# e-ink-display-v003.net
KiCad netlist of a schematic drawn in EAGLE
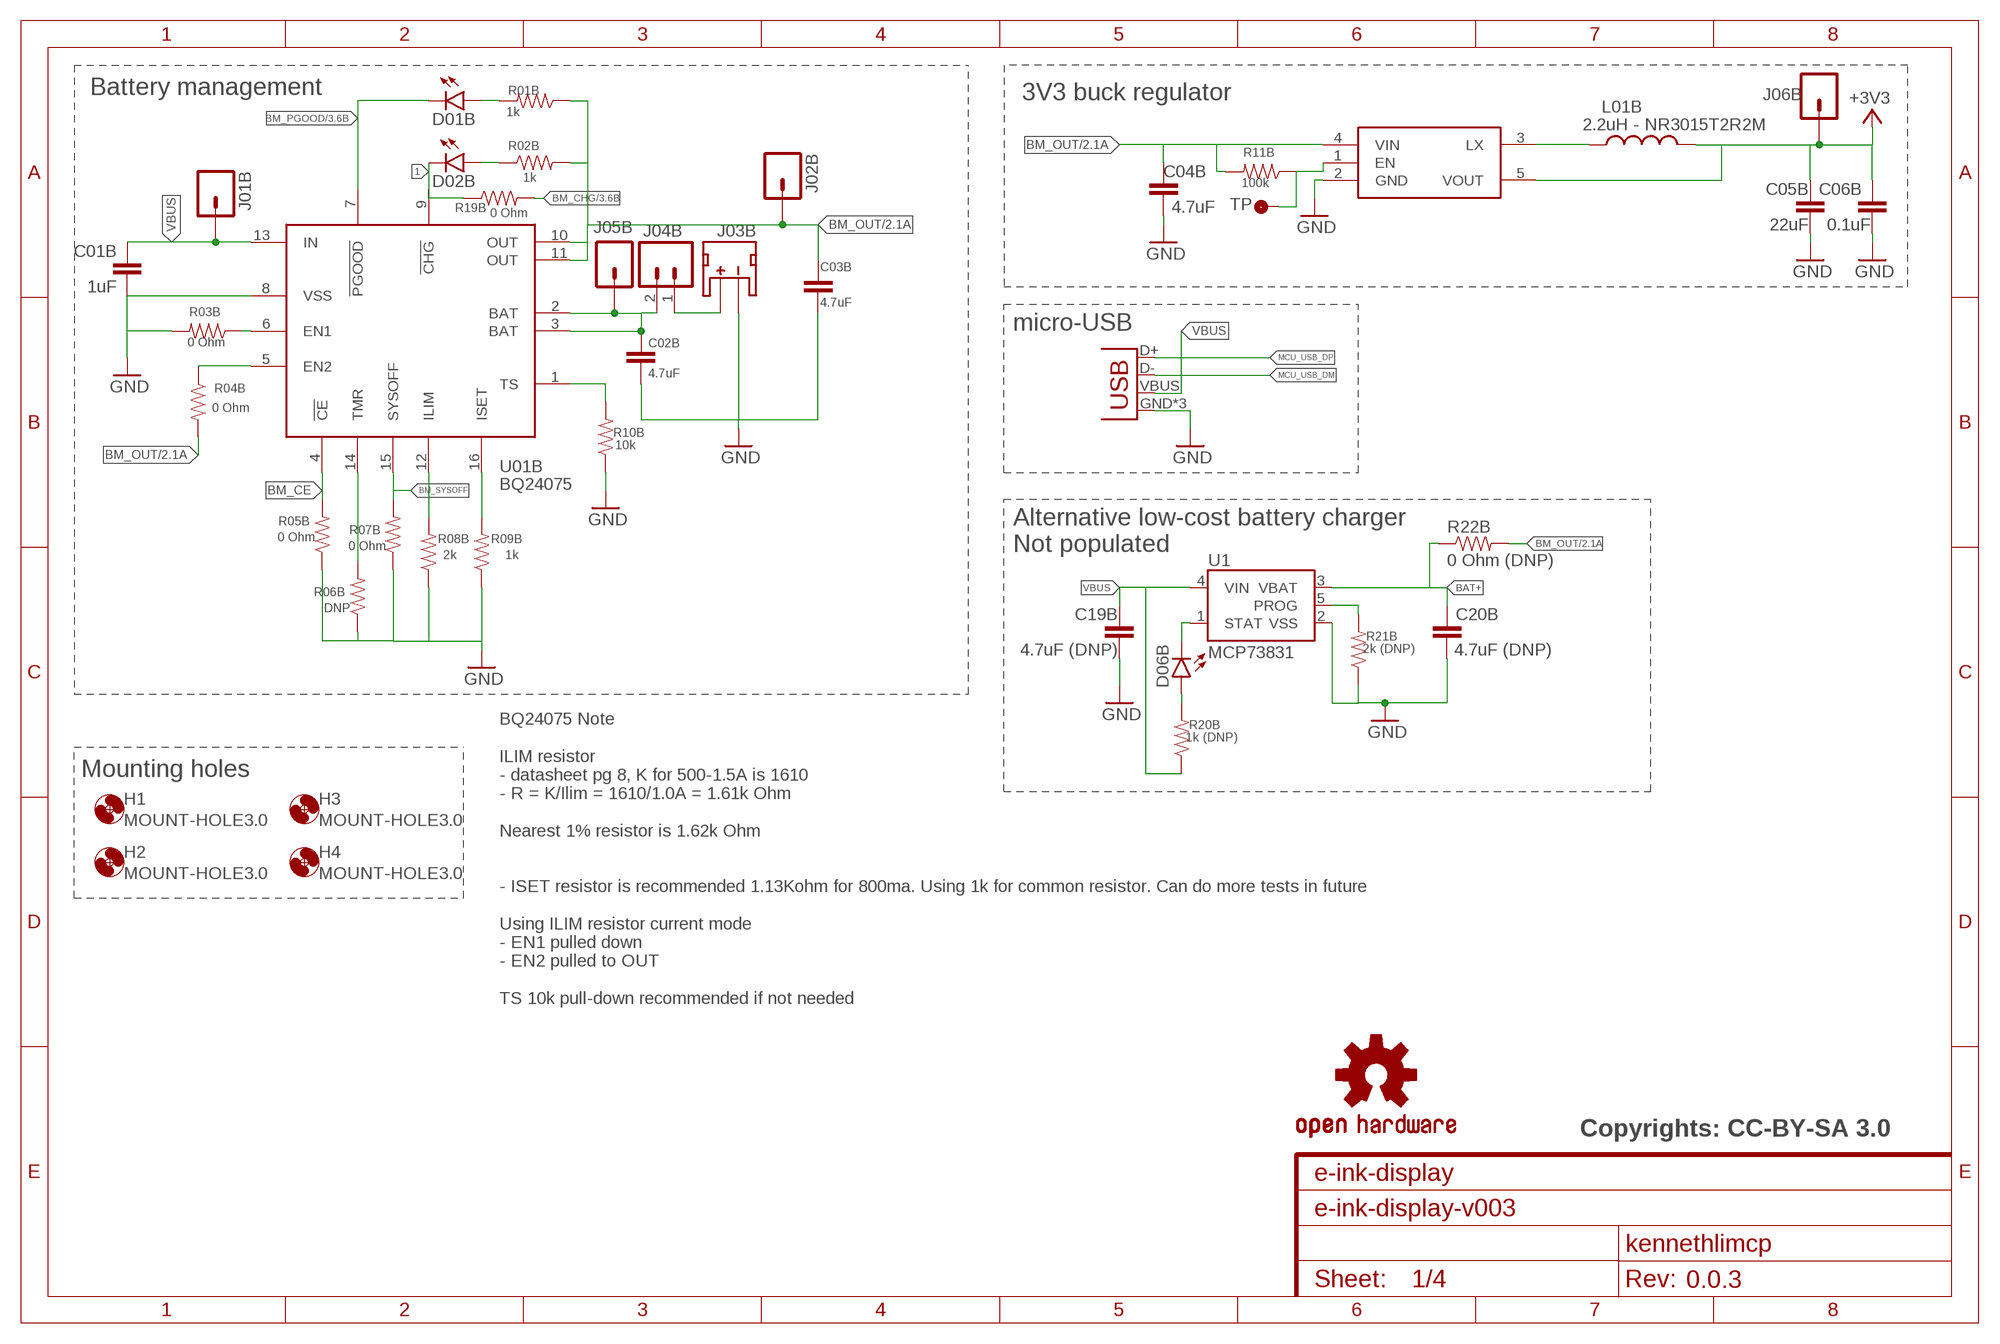
[diagram p0: schematic, sheet 1]
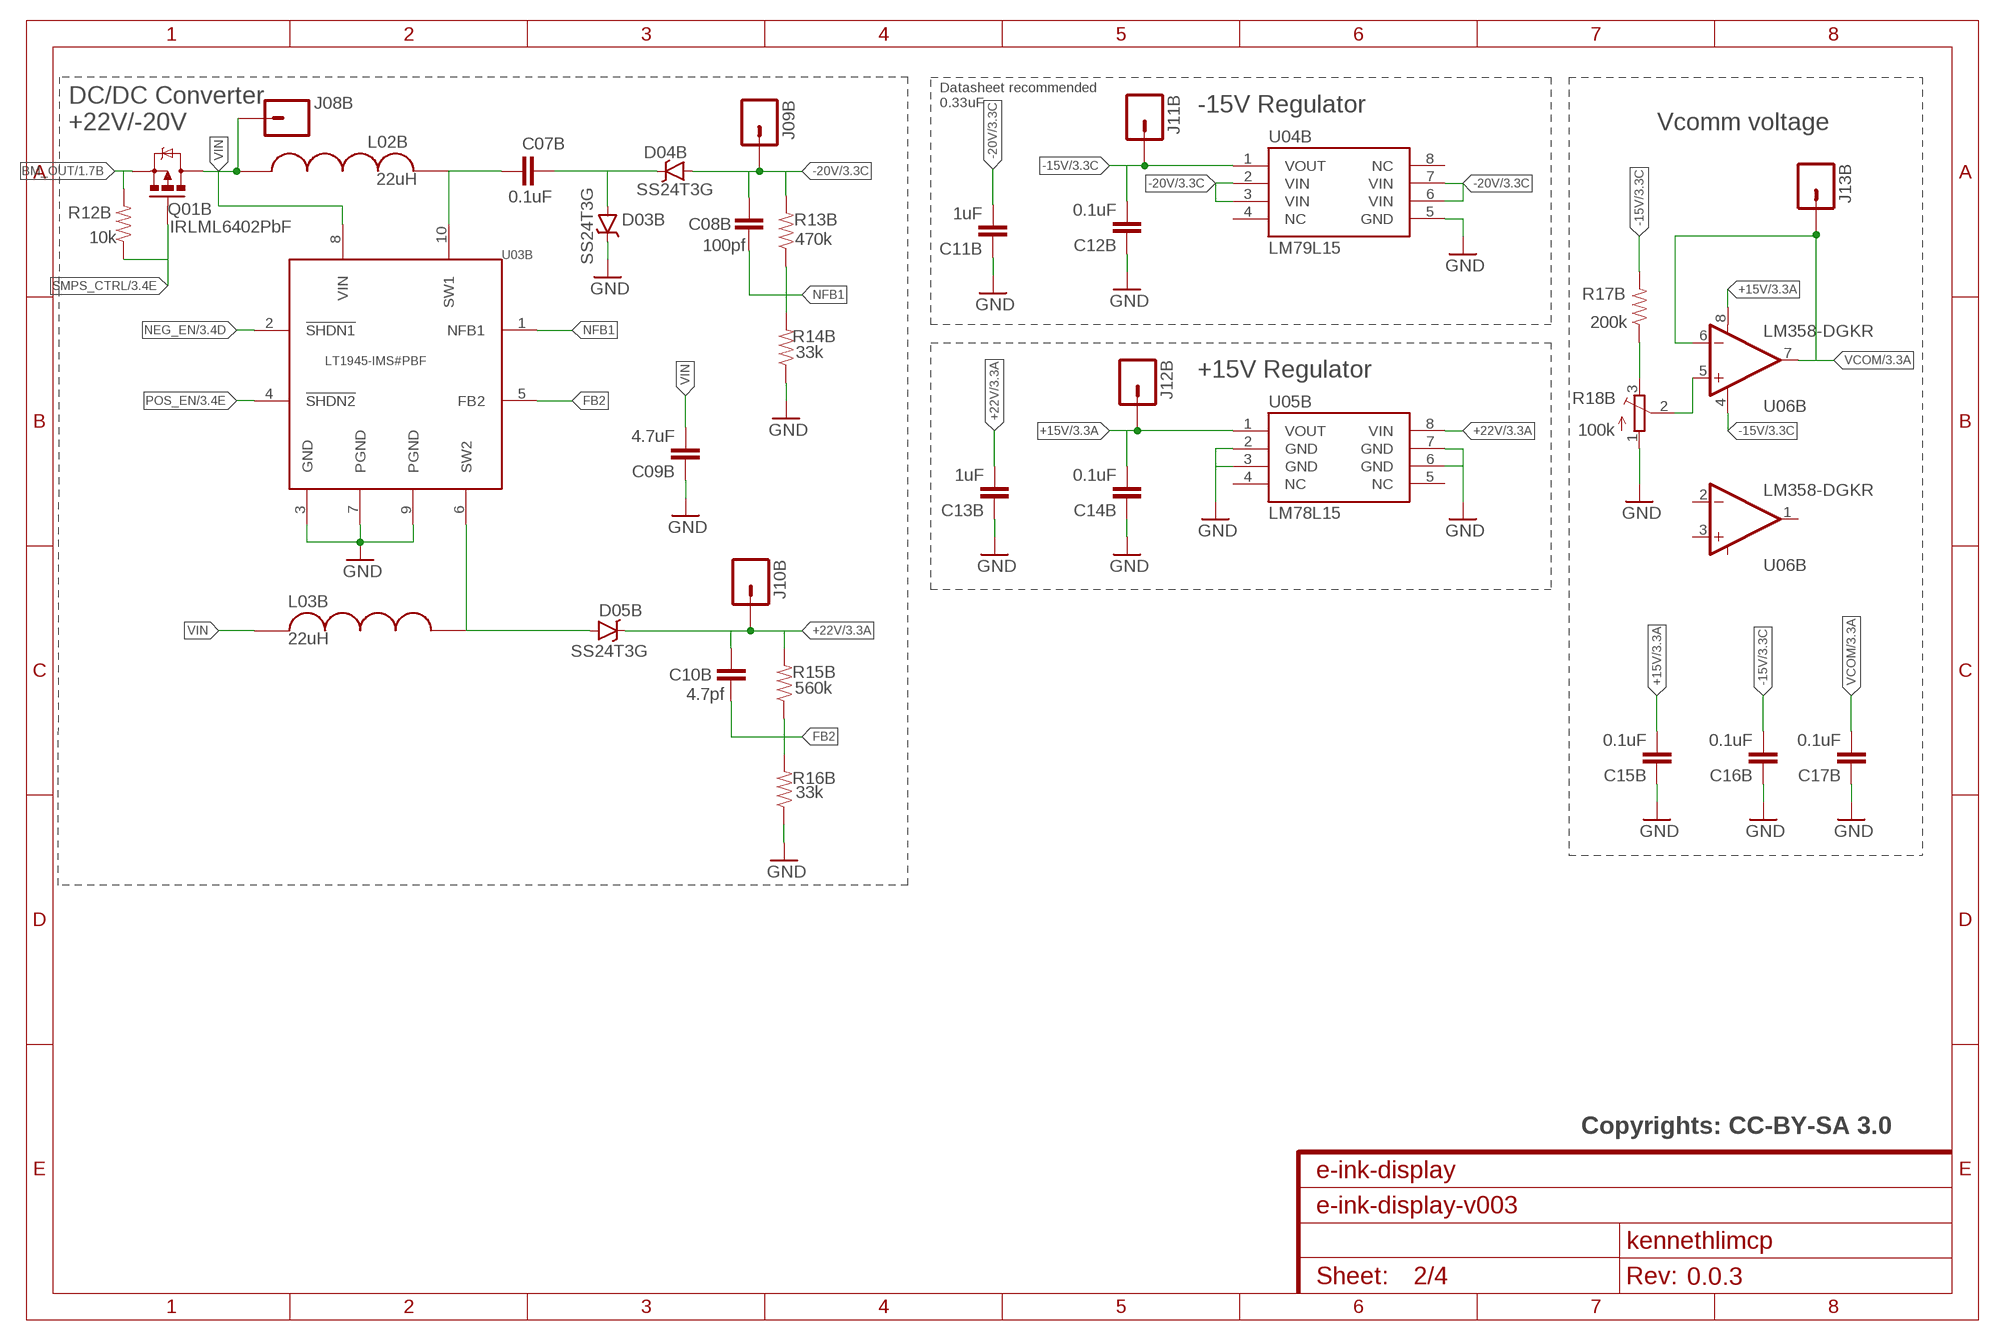
[diagram p1: schematic, sheet 2]
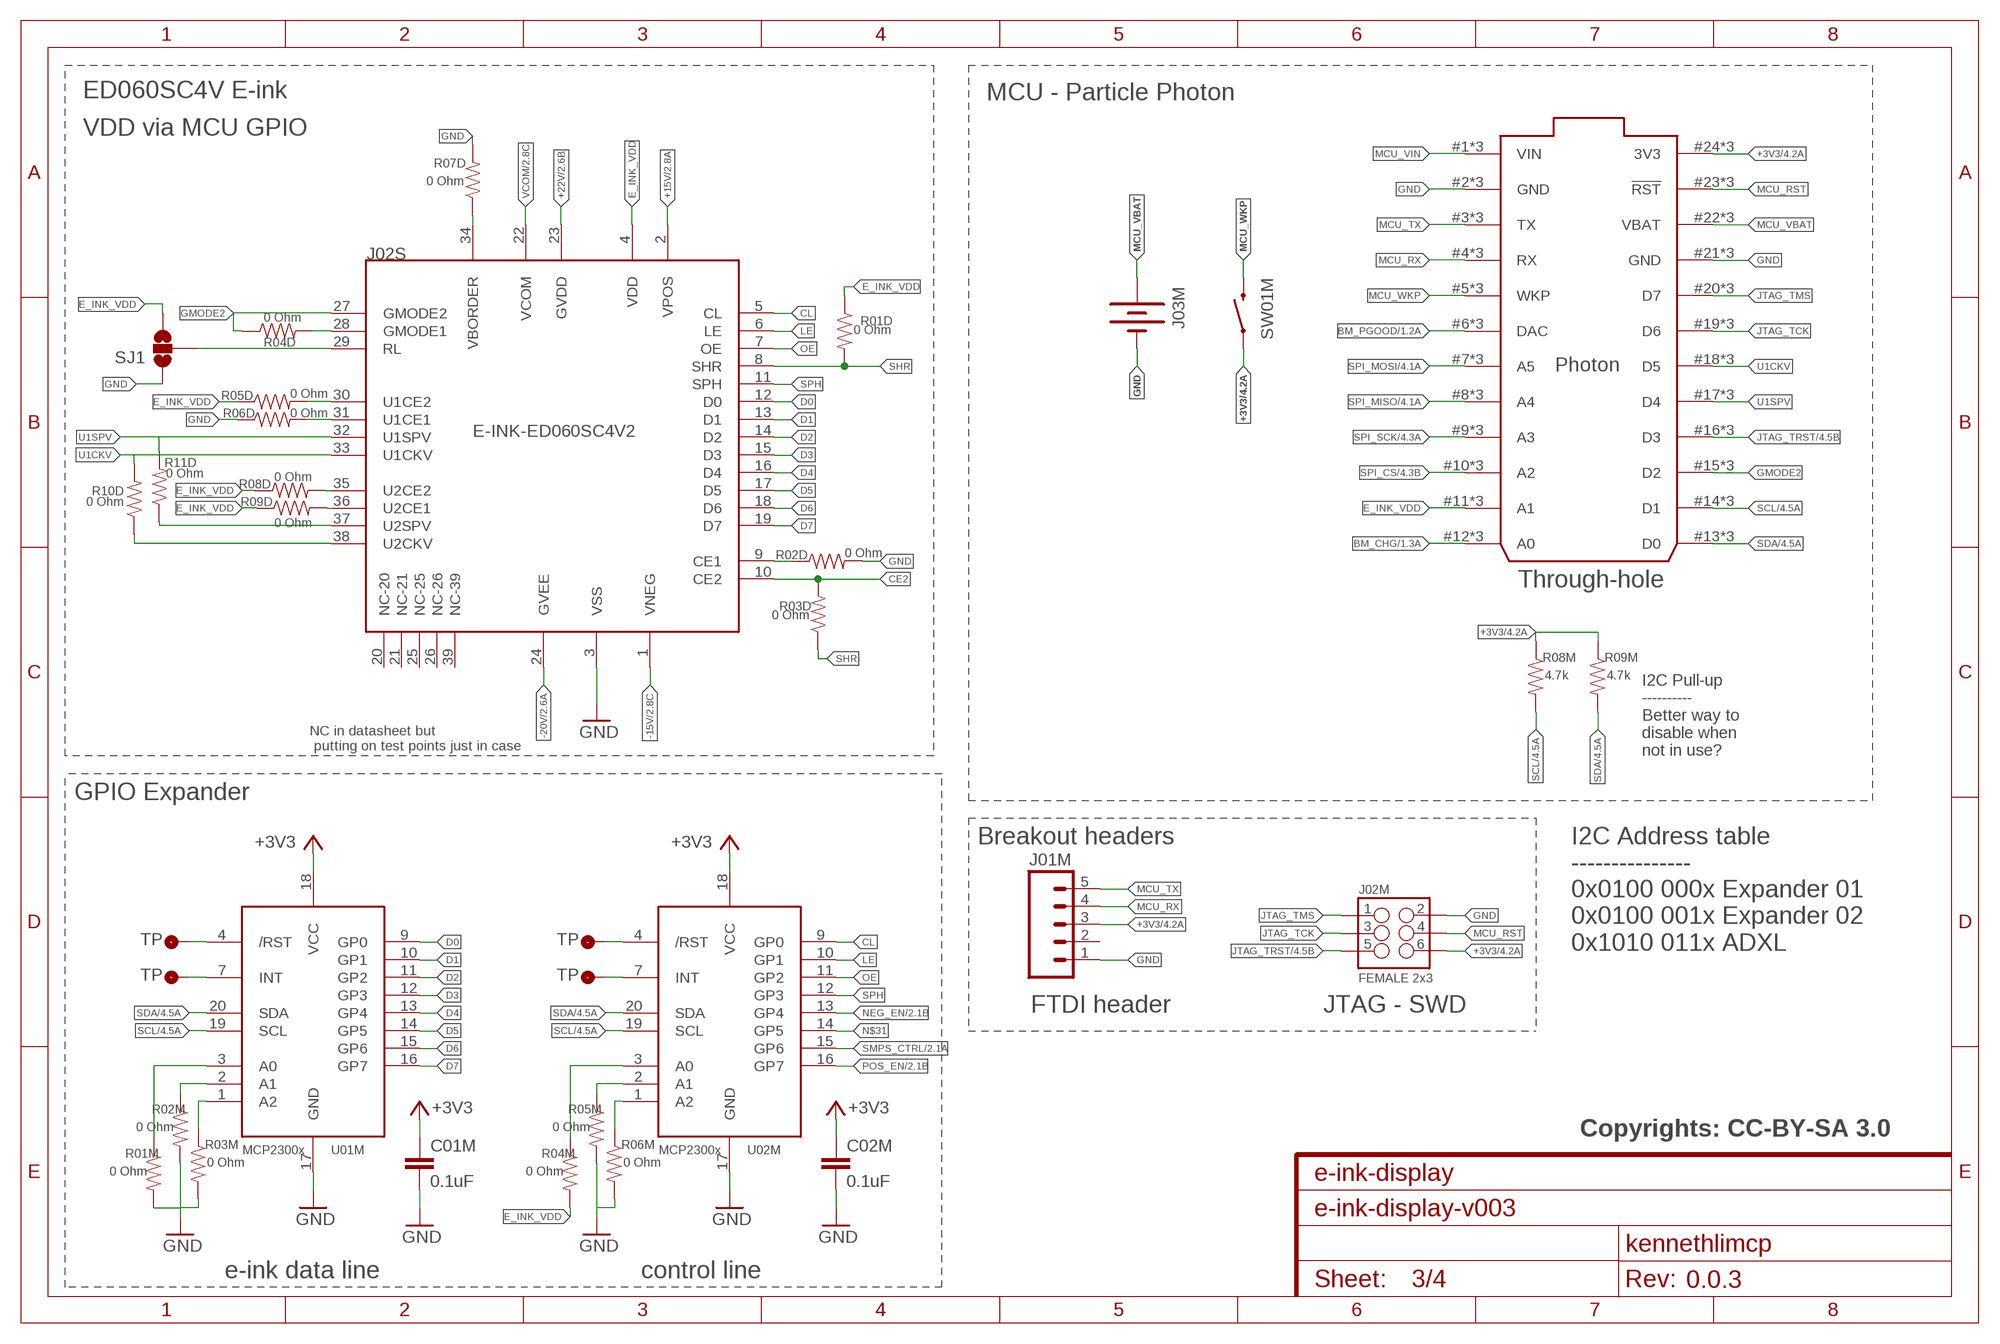
[diagram p2: schematic, sheet 3]
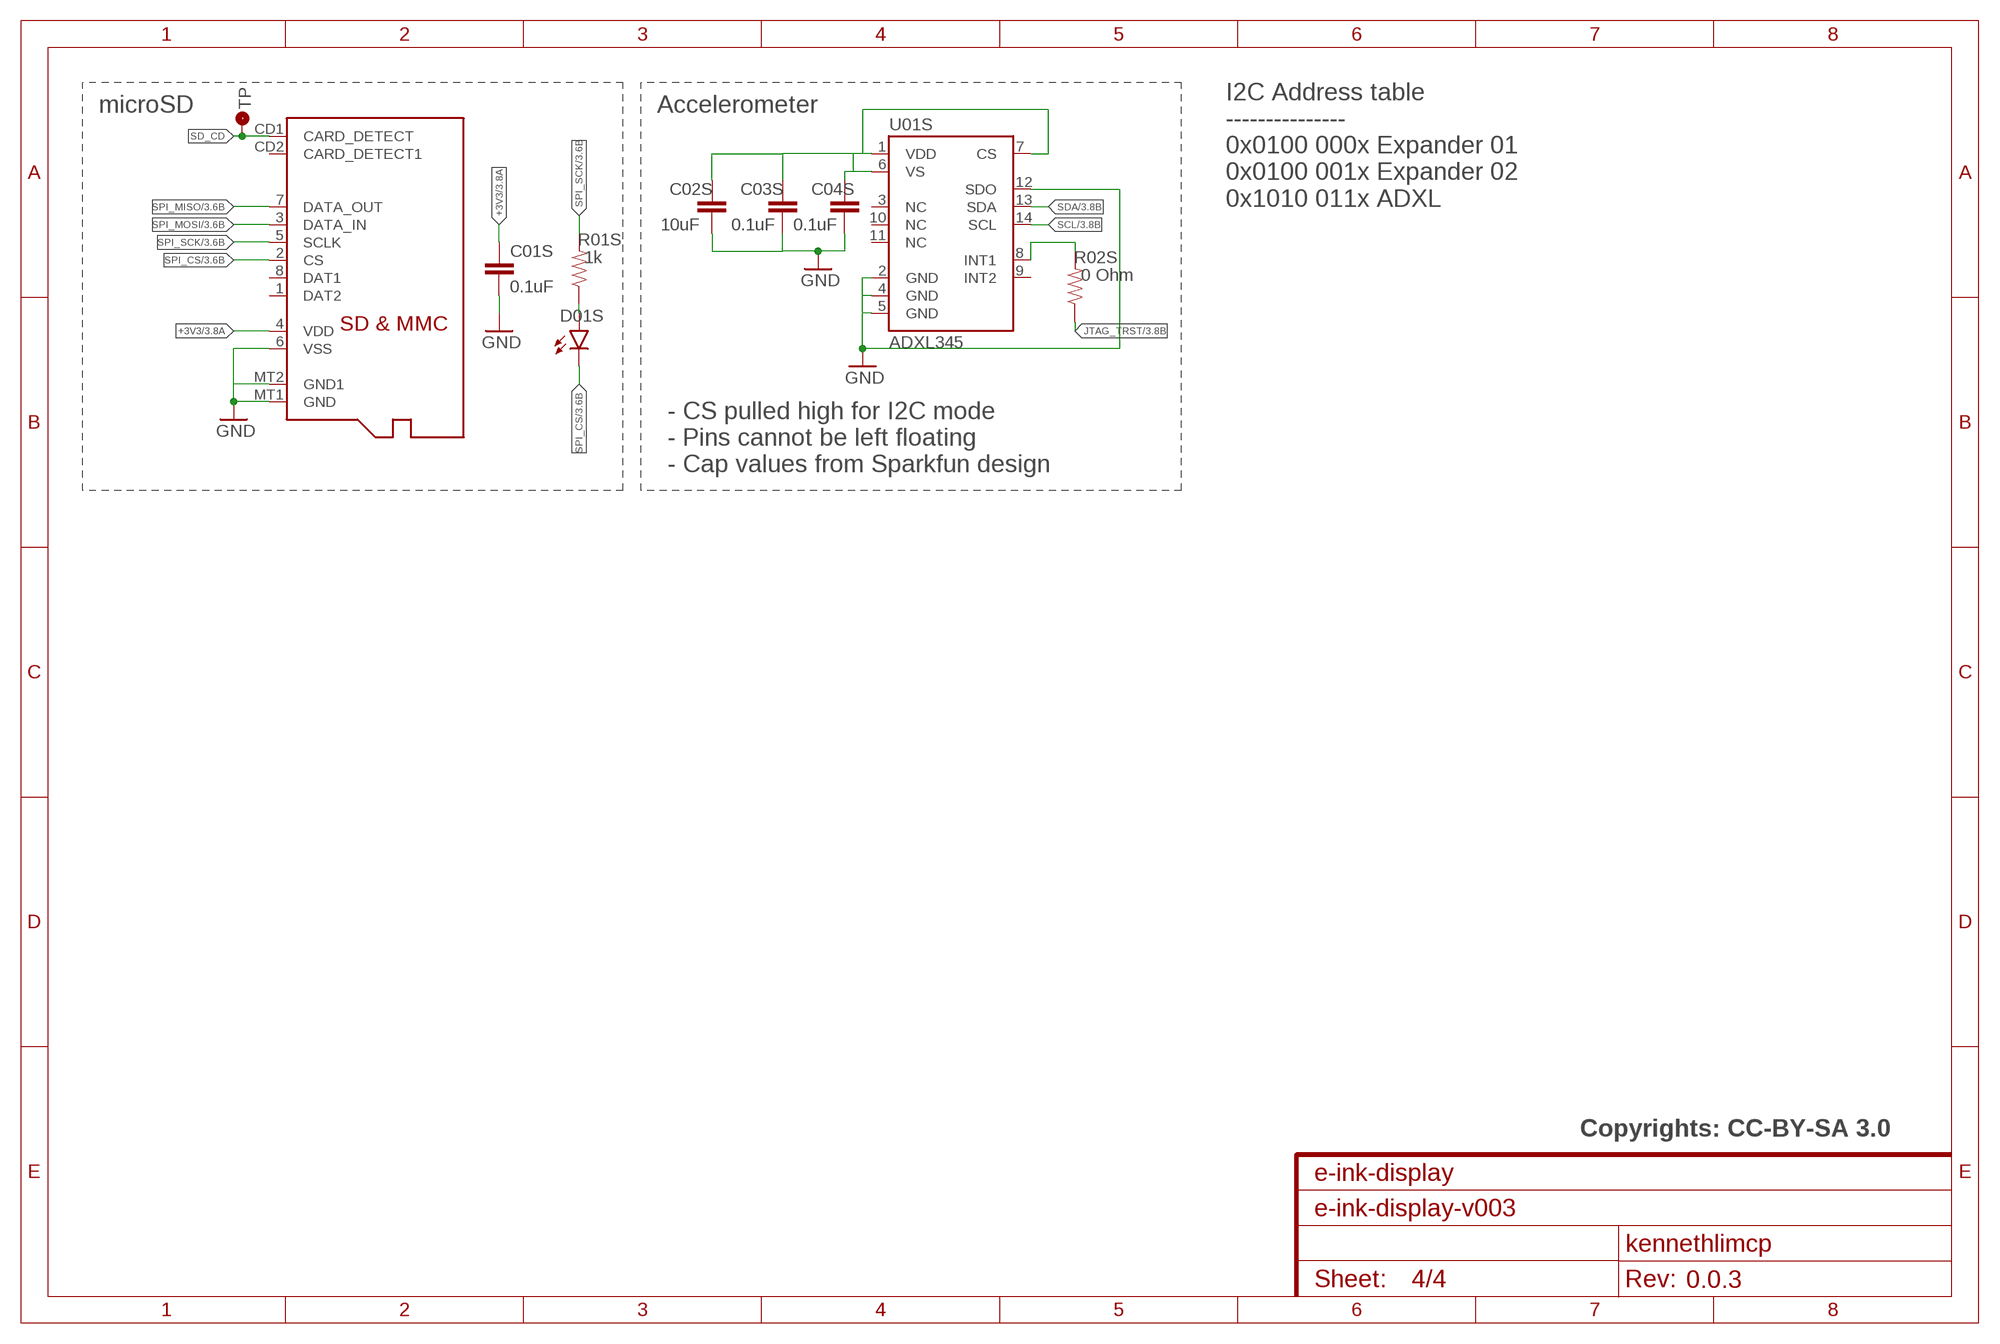
[diagram p3: schematic, sheet 4]

(export (version "E")
  (design (tool "Eeschema 10.0.6"))
  (components
    (comp (ref "C01M")
      (value "0.1uF")
      (footprint "eagle-import:0603-CAP")
      (libsource (lib "eagle-import") (part "CAP0603-CAP"))
    )
    (comp (ref "C02M")
      (value "0.1uF")
      (footprint "eagle-import:0603-CAP")
      (libsource (lib "eagle-import") (part "CAP0603-CAP"))
    )
    (comp (ref "J01M")
      (value "M05PTH")
      (footprint "eagle-import:1X05")
      (libsource (lib "eagle-import") (part "M05PTH"))
    )
    (comp (ref "J02M")
      (value "FEMALE 2x3")
      (footprint "eagle-import:2X3")
      (libsource (lib "eagle-import") (part "M03X2FEMALE"))
    )
    (comp (ref "J02S")
      (value "E-INK-ED060SC4V2")
      (footprint "eagle-import:FPC-0.3-39")
      (libsource (lib "eagle-import") (part "E-INK-ED060SC4V2"))
    )
    (comp (ref "J03M")
      (value "BATTERY20PTH")
      (footprint "eagle-import:BATTCOM_20MM_PTH")
      (libsource (lib "eagle-import") (part "BATTERY20PTH"))
    )
    (comp (ref "R01D")
      (value "0 Ohm")
      (footprint "eagle-import:0603-RES")
      (libsource (lib "eagle-import") (part "RESISTOR0603-RES"))
    )
    (comp (ref "R01M")
      (value "0 Ohm")
      (footprint "eagle-import:0603-RES")
      (libsource (lib "eagle-import") (part "RESISTOR0603-RES"))
    )
    (comp (ref "R02D")
      (value "0 Ohm")
      (footprint "eagle-import:0603-RES")
      (libsource (lib "eagle-import") (part "RESISTOR0603-RES"))
    )
    (comp (ref "R02M")
      (value "0 Ohm")
      (footprint "eagle-import:0603-RES")
      (libsource (lib "eagle-import") (part "RESISTOR0603-RES"))
    )
    (comp (ref "R03D")
      (value "0 Ohm")
      (footprint "eagle-import:0603-RES")
      (libsource (lib "eagle-import") (part "RESISTOR0603-RES"))
    )
    (comp (ref "R03M")
      (value "0 Ohm")
      (footprint "eagle-import:0603-RES")
      (libsource (lib "eagle-import") (part "RESISTOR0603-RES"))
    )
    (comp (ref "R04D")
      (value "0 Ohm")
      (footprint "eagle-import:0603-RES")
      (libsource (lib "eagle-import") (part "RESISTOR0603-RES"))
    )
    (comp (ref "R04M")
      (value "0 Ohm")
      (footprint "eagle-import:0603-RES")
      (libsource (lib "eagle-import") (part "RESISTOR0603-RES"))
    )
    (comp (ref "R05D")
      (value "0 Ohm")
      (footprint "eagle-import:0603-RES")
      (libsource (lib "eagle-import") (part "RESISTOR0603-RES"))
    )
    (comp (ref "R05M")
      (value "0 Ohm")
      (footprint "eagle-import:0603-RES")
      (libsource (lib "eagle-import") (part "RESISTOR0603-RES"))
    )
    (comp (ref "R06D")
      (value "0 Ohm")
      (footprint "eagle-import:0603-RES")
      (libsource (lib "eagle-import") (part "RESISTOR0603-RES"))
    )
    (comp (ref "R06M")
      (value "0 Ohm")
      (footprint "eagle-import:0603-RES")
      (libsource (lib "eagle-import") (part "RESISTOR0603-RES"))
    )
    (comp (ref "R07D")
      (value "0 Ohm")
      (footprint "eagle-import:0603-RES")
      (libsource (lib "eagle-import") (part "RESISTOR0603-RES"))
    )
    (comp (ref "R08D")
      (value "0 Ohm")
      (footprint "eagle-import:0603-RES")
      (libsource (lib "eagle-import") (part "RESISTOR0603-RES"))
    )
    (comp (ref "R08M")
      (value "4.7k")
      (footprint "eagle-import:0603-RES")
      (libsource (lib "eagle-import") (part "RESISTOR0603-RES"))
    )
    (comp (ref "R09D")
      (value "0 Ohm")
      (footprint "eagle-import:0603-RES")
      (libsource (lib "eagle-import") (part "RESISTOR0603-RES"))
    )
    (comp (ref "R09M")
      (value "4.7k")
      (footprint "eagle-import:0603-RES")
      (libsource (lib "eagle-import") (part "RESISTOR0603-RES"))
    )
    (comp (ref "R10D")
      (value "0 Ohm")
      (footprint "eagle-import:0603-RES")
      (libsource (lib "eagle-import") (part "RESISTOR0603-RES"))
    )
    (comp (ref "R11D")
      (value "0 Ohm")
      (footprint "eagle-import:0603-RES")
      (libsource (lib "eagle-import") (part "RESISTOR0603-RES"))
    )
    (comp (ref "SJ1")
      (value "SOLDERJUMPER_2WAYT")
      (footprint "eagle-import:SJ_2")
      (libsource (lib "eagle-import") (part "SOLDERJUMPER_2WAYT"))
    )
    (comp (ref "SW01M")
      (value "SWITCH-MOMENTARY-2PTH")
      (footprint "eagle-import:TACTILE-PTH")
      (libsource (lib "eagle-import") (part "SWITCH-MOMENTARY-2PTH"))
    )
    (comp (ref "U$1")
      (value "TP1")
      (footprint "eagle-import:TP35_BOT")
      (libsource (lib "eagle-import") (part "TP1"))
    )
    (comp (ref "U$2")
      (value "TP1")
      (footprint "eagle-import:TP35_BOT")
      (libsource (lib "eagle-import") (part "TP1"))
    )
    (comp (ref "U$3")
      (value "TP1")
      (footprint "eagle-import:TP35_BOT")
      (libsource (lib "eagle-import") (part "TP1"))
    )
    (comp (ref "U$4")
      (value "TP1")
      (footprint "eagle-import:TP35_BOT")
      (libsource (lib "eagle-import") (part "TP1"))
    )
    (comp (ref "U01M")
      (value "MCP2300X/QFN")
      (footprint "eagle-import:QFN-20(4X4)")
      (libsource (lib "eagle-import") (part "MCP2300X/QFN"))
    )
    (comp (ref "U02M")
      (value "MCP2300X/QFN")
      (footprint "eagle-import:QFN-20(4X4)")
      (libsource (lib "eagle-import") (part "MCP2300X/QFN"))
    )
    (comp (ref "U03M")
      (value "PHOTON_WITH_STACKABLE_HEADERS")
      (footprint "eagle-import:PHOTON_STACKABLE")
      (libsource (lib "eagle-import") (part "PHOTON_WITH_STACKABLE_HEADERS"))
    )
    (comp (ref "C01S")
      (value "0.1uF")
      (footprint "eagle-import:0603-CAP")
      (libsource (lib "eagle-import") (part "CAP0603-CAP"))
    )
    (comp (ref "C02S")
      (value "10uF")
      (footprint "eagle-import:0603-CAP")
      (libsource (lib "eagle-import") (part "CAP0603-CAP"))
    )
    (comp (ref "C03S")
      (value "0.1uF")
      (footprint "eagle-import:0603-CAP")
      (libsource (lib "eagle-import") (part "CAP0603-CAP"))
    )
    (comp (ref "C04S")
      (value "0.1uF")
      (footprint "eagle-import:0603-CAP")
      (libsource (lib "eagle-import") (part "CAP0603-CAP"))
    )
    (comp (ref "D01S")
      (value "LED0603")
      (footprint "eagle-import:LED-0603")
      (libsource (lib "eagle-import") (part "LED0603"))
    )
    (comp (ref "J01S")
      (value "MICROSD")
      (footprint "eagle-import:MICROSD")
      (libsource (lib "eagle-import") (part "MICROSD"))
    )
    (comp (ref "R01S")
      (value "1k")
      (footprint "eagle-import:0603-RES")
      (libsource (lib "eagle-import") (part "SparkFun-Resistors_RESISTOR0603-RES"))
    )
    (comp (ref "R02S")
      (value "0 Ohm")
      (footprint "eagle-import:0603-RES")
      (libsource (lib "eagle-import") (part "RESISTOR0603"))
    )
    (comp (ref "U$5")
      (value "TP3")
      (footprint "eagle-import:TP60_BOT")
      (libsource (lib "eagle-import") (part "TP3"))
    )
    (comp (ref "U01S")
      (value "ADXL345")
      (footprint "eagle-import:LGA14")
      (libsource (lib "eagle-import") (part "ADXL345"))
    )
    (comp (ref "C01B")
      (value "1uF")
      (footprint "eagle-import:0603-CAP")
      (libsource (lib "eagle-import") (part "CAP0603-CAP"))
    )
    (comp (ref "C02B")
      (value "4.7uF")
      (footprint "eagle-import:0603-CAP")
      (libsource (lib "eagle-import") (part "CAP0603-CAP"))
    )
    (comp (ref "C03B")
      (value "4.7uF")
      (footprint "eagle-import:0603-CAP")
      (libsource (lib "eagle-import") (part "CAP0603-CAP"))
    )
    (comp (ref "C04B")
      (value "4.7uF")
      (footprint "eagle-import:0603-CAP")
      (libsource (lib "eagle-import") (part "CAP0603-CAP"))
    )
    (comp (ref "C05B")
      (value "22uF")
      (footprint "eagle-import:0603-CAP")
      (libsource (lib "eagle-import") (part "CAP0603-CAP"))
    )
    (comp (ref "C06B")
      (value "0.1uF")
      (footprint "eagle-import:0603-CAP")
      (libsource (lib "eagle-import") (part "CAP0603-CAP"))
    )
    (comp (ref "C19B")
      (value "4.7uF (DNP)")
      (footprint "eagle-import:0603-CAP")
      (libsource (lib "eagle-import") (part "CAP0603-CAP"))
    )
    (comp (ref "C20B")
      (value "4.7uF (DNP)")
      (footprint "eagle-import:0603-CAP")
      (libsource (lib "eagle-import") (part "CAP0603-CAP"))
    )
    (comp (ref "D01B")
      (value "LED0603")
      (footprint "eagle-import:LED-0603")
      (libsource (lib "eagle-import") (part "LED0603"))
    )
    (comp (ref "D02B")
      (value "LED0603")
      (footprint "eagle-import:LED-0603")
      (libsource (lib "eagle-import") (part "LED0603"))
    )
    (comp (ref "D06B")
      (value "LED0603")
      (footprint "eagle-import:LED-0603")
      (libsource (lib "eagle-import") (part "LED0603"))
    )
    (comp (ref "H1")
      (value "MOUNT-HOLE3.0")
      (footprint "eagle-import:3,0")
      (libsource (lib "eagle-import") (part "MOUNT-HOLE3.0"))
    )
    (comp (ref "H2")
      (value "MOUNT-HOLE3.0")
      (footprint "eagle-import:3,0")
      (libsource (lib "eagle-import") (part "MOUNT-HOLE3.0"))
    )
    (comp (ref "H3")
      (value "MOUNT-HOLE3.0")
      (footprint "eagle-import:3,0")
      (libsource (lib "eagle-import") (part "MOUNT-HOLE3.0"))
    )
    (comp (ref "H4")
      (value "MOUNT-HOLE3.0")
      (footprint "eagle-import:3,0")
      (libsource (lib "eagle-import") (part "MOUNT-HOLE3.0"))
    )
    (comp (ref "J01B")
      (value "M01PTH")
      (footprint "eagle-import:1X01")
      (libsource (lib "eagle-import") (part "M01PTH"))
    )
    (comp (ref "J02B")
      (value "M01PTH")
      (footprint "eagle-import:1X01")
      (libsource (lib "eagle-import") (part "M01PTH"))
    )
    (comp (ref "J03B")
      (value "JST_2MM_MALE")
      (footprint "eagle-import:JST-2-SMD")
      (libsource (lib "eagle-import") (part "JST_2MM_MALE"))
    )
    (comp (ref "J04B")
      (value "M02PTH")
      (footprint "eagle-import:1X02")
      (libsource (lib "eagle-import") (part "M02PTH"))
    )
    (comp (ref "J05B")
      (value "M01PTH")
      (footprint "eagle-import:1X01")
      (libsource (lib "eagle-import") (part "M01PTH"))
    )
    (comp (ref "J06B")
      (value "M01PTH")
      (footprint "eagle-import:1X01")
      (libsource (lib "eagle-import") (part "M01PTH"))
    )
    (comp (ref "J07B")
      (value "USBUSB-MICROB-SLOT-HOLE")
      (footprint "eagle-import:USB-MICROB-SLOT-HOLE")
      (libsource (lib "eagle-import") (part "USBUSB-MICROB-SLOT-HOLE"))
    )
    (comp (ref "L01B")
      (value "2.2uH - NR3015T2R2M")
      (footprint "eagle-import:INDUCTOR-NR3015")
      (libsource (lib "eagle-import") (part "INDUCTOR-SPARKFUNNR3015T4R7M"))
    )
    (comp (ref "LOGO1")
      (value "OSHW-LOGOPAD")
      (footprint "eagle-import:OSHW-LOGO-M-PAD")
      (libsource (lib "eagle-import") (part "OSHW-LOGOPAD"))
    )
    (comp (ref "R01B")
      (value "1k")
      (footprint "eagle-import:0603-RES")
      (libsource (lib "eagle-import") (part "SparkFun-Resistors_RESISTOR0603-RES"))
    )
    (comp (ref "R02B")
      (value "1k")
      (footprint "eagle-import:0603-RES")
      (libsource (lib "eagle-import") (part "SparkFun-Resistors_RESISTOR0603-RES"))
    )
    (comp (ref "R03B")
      (value "0 Ohm")
      (footprint "eagle-import:0603-RES")
      (libsource (lib "eagle-import") (part "SparkFun-Resistors_RESISTOR0603-RES"))
    )
    (comp (ref "R04B")
      (value "0 Ohm")
      (footprint "eagle-import:0603-RES")
      (libsource (lib "eagle-import") (part "RESISTOR0603"))
    )
    (comp (ref "R05B")
      (value "0 Ohm")
      (footprint "eagle-import:0603-RES")
      (libsource (lib "eagle-import") (part "RESISTOR0603"))
    )
    (comp (ref "R06B")
      (value "DNP")
      (footprint "eagle-import:0603-RES")
      (libsource (lib "eagle-import") (part "RESISTOR0603"))
    )
    (comp (ref "R07B")
      (value "0 Ohm")
      (footprint "eagle-import:0603-RES")
      (libsource (lib "eagle-import") (part "RESISTOR0603"))
    )
    (comp (ref "R08B")
      (value "2k")
      (footprint "eagle-import:0603-RES")
      (libsource (lib "eagle-import") (part "RESISTOR0603"))
    )
    (comp (ref "R09B")
      (value "1k")
      (footprint "eagle-import:0603-RES")
      (libsource (lib "eagle-import") (part "SparkFun-Resistors_RESISTOR0603-RES"))
    )
    (comp (ref "R10B")
      (value "10k")
      (footprint "eagle-import:0603-RES")
      (libsource (lib "eagle-import") (part "RESISTOR0603"))
    )
    (comp (ref "R11B")
      (value "100k")
      (footprint "eagle-import:0603-RES")
      (libsource (lib "eagle-import") (part "RESISTOR0603"))
    )
    (comp (ref "R19B")
      (value "0 Ohm")
      (footprint "eagle-import:0603-RES")
      (libsource (lib "eagle-import") (part "RESISTOR0603"))
    )
    (comp (ref "R20B")
      (value "1k (DNP)")
      (footprint "eagle-import:0603-RES")
      (libsource (lib "eagle-import") (part "RESISTOR0603"))
    )
    (comp (ref "R21B")
      (value "2k (DNP)")
      (footprint "eagle-import:0603-RES")
      (libsource (lib "eagle-import") (part "RESISTOR0603"))
    )
    (comp (ref "R22B")
      (value "0 Ohm (DNP)")
      (footprint "eagle-import:1206")
      (libsource (lib "eagle-import") (part "SparkFun-Resistors_RESISTOR1206"))
    )
    (comp (ref "TP01B")
      (value "TP1")
      (footprint "eagle-import:TP35_BOT")
      (libsource (lib "eagle-import") (part "TP1"))
    )
    (comp (ref "U1")
      (value "MCP73831")
      (footprint "eagle-import:SOT23-5")
      (libsource (lib "eagle-import") (part "MCP73831"))
    )
    (comp (ref "U01B")
      (value "BQ24075")
      (footprint "eagle-import:QFN-16")
      (libsource (lib "eagle-import") (part "BQ24075"))
    )
    (comp (ref "U02B")
      (value "R8008-33")
      (footprint "eagle-import:SOT23-5")
      (libsource (lib "eagle-import") (part "R8008-33"))
    )
    (comp (ref "C07B")
      (value "0.1uF")
      (footprint "eagle-import:0603-CAP")
      (libsource (lib "eagle-import") (part "CAP0603-CAP"))
    )
    (comp (ref "C08B")
      (value "100pf")
      (footprint "eagle-import:0603-CAP")
      (libsource (lib "eagle-import") (part "CAP0603-CAP"))
    )
    (comp (ref "C09B")
      (value "4.7uF")
      (footprint "eagle-import:0603-CAP")
      (libsource (lib "eagle-import") (part "CAP0603-CAP"))
    )
    (comp (ref "C10B")
      (value "4.7pf")
      (footprint "eagle-import:0603-CAP")
      (libsource (lib "eagle-import") (part "CAP0603-CAP"))
    )
    (comp (ref "C11B")
      (value "1uF")
      (footprint "eagle-import:0603-CAP")
      (libsource (lib "eagle-import") (part "CAP0603-CAP"))
    )
    (comp (ref "C12B")
      (value "0.1uF")
      (footprint "eagle-import:0603-CAP")
      (libsource (lib "eagle-import") (part "CAP0603-CAP"))
    )
    (comp (ref "C13B")
      (value "1uF")
      (footprint "eagle-import:0603-CAP")
      (libsource (lib "eagle-import") (part "CAP0603-CAP"))
    )
    (comp (ref "C14B")
      (value "0.1uF")
      (footprint "eagle-import:0603-CAP")
      (libsource (lib "eagle-import") (part "CAP0603-CAP"))
    )
    (comp (ref "C15B")
      (value "0.1uF")
      (footprint "eagle-import:0603-CAP")
      (libsource (lib "eagle-import") (part "CAP0603-CAP"))
    )
    (comp (ref "C16B")
      (value "0.1uF")
      (footprint "eagle-import:0603-CAP")
      (libsource (lib "eagle-import") (part "CAP0603-CAP"))
    )
    (comp (ref "C17B")
      (value "0.1uF")
      (footprint "eagle-import:0603-CAP")
      (libsource (lib "eagle-import") (part "CAP0603-CAP"))
    )
    (comp (ref "D03B")
      (value "SS24T3G")
      (footprint "eagle-import:SMA-DIODE")
      (libsource (lib "eagle-import") (part "SS24T3G"))
    )
    (comp (ref "D04B")
      (value "SS24T3G")
      (footprint "eagle-import:SMA-DIODE")
      (libsource (lib "eagle-import") (part "SS24T3G"))
    )
    (comp (ref "D05B")
      (value "SS24T3G")
      (footprint "eagle-import:SMA-DIODE")
      (libsource (lib "eagle-import") (part "SS24T3G"))
    )
    (comp (ref "J08B")
      (value "M01PTH")
      (footprint "eagle-import:1X01")
      (libsource (lib "eagle-import") (part "M01PTH"))
    )
    (comp (ref "J09B")
      (value "M01PTH")
      (footprint "eagle-import:1X01")
      (libsource (lib "eagle-import") (part "M01PTH"))
    )
    (comp (ref "J10B")
      (value "M01PTH")
      (footprint "eagle-import:1X01")
      (libsource (lib "eagle-import") (part "M01PTH"))
    )
    (comp (ref "J11B")
      (value "M01PTH")
      (footprint "eagle-import:1X01")
      (libsource (lib "eagle-import") (part "M01PTH"))
    )
    (comp (ref "J12B")
      (value "M01PTH")
      (footprint "eagle-import:1X01")
      (libsource (lib "eagle-import") (part "M01PTH"))
    )
    (comp (ref "J13B")
      (value "M01PTH")
      (footprint "eagle-import:1X01")
      (libsource (lib "eagle-import") (part "M01PTH"))
    )
    (comp (ref "L02B")
      (value "22uH")
      (footprint "eagle-import:4040(1515)")
      (libsource (lib "eagle-import") (part "INDUCTOR"))
    )
    (comp (ref "L03B")
      (value "22uH")
      (footprint "eagle-import:4040(1515)")
      (libsource (lib "eagle-import") (part "INDUCTOR"))
    )
    (comp (ref "Q01B")
      (value "IRLML6402PbF")
      (footprint "eagle-import:SOT23-3")
      (libsource (lib "eagle-import") (part "MOSFET-PCHANNELSMD"))
    )
    (comp (ref "R12B")
      (value "10k")
      (footprint "eagle-import:0603-RES")
      (libsource (lib "eagle-import") (part "RESISTOR0603"))
    )
    (comp (ref "R13B")
      (value "470k")
      (footprint "eagle-import:0603-RES")
      (libsource (lib "eagle-import") (part "RESISTOR0603"))
    )
    (comp (ref "R14B")
      (value "33k")
      (footprint "eagle-import:0603-RES")
      (libsource (lib "eagle-import") (part "RESISTOR0603"))
    )
    (comp (ref "R15B")
      (value "560k")
      (footprint "eagle-import:0603-RES")
      (libsource (lib "eagle-import") (part "RESISTOR0603"))
    )
    (comp (ref "R16B")
      (value "33k")
      (footprint "eagle-import:0603-RES")
      (libsource (lib "eagle-import") (part "RESISTOR0603"))
    )
    (comp (ref "R17B")
      (value "200k")
      (footprint "eagle-import:0603-RES")
      (libsource (lib "eagle-import") (part "RESISTOR0603"))
    )
    (comp (ref "R18B")
      (value "100k")
      (footprint "eagle-import:TC33X")
      (libsource (lib "eagle-import") (part "TRIMPOTTC33X"))
    )
    (comp (ref "U03B")
      (value "LT1945-IMS#PBF")
      (footprint "eagle-import:MSOP-10")
      (libsource (lib "eagle-import") (part "LT1945-IMS#PBF"))
    )
    (comp (ref "U04B")
      (value "LM79L15")
      (footprint "eagle-import:SO08")
      (libsource (lib "eagle-import") (part "LM79L15"))
    )
    (comp (ref "U05B")
      (value "LM78L15")
      (footprint "eagle-import:SO08")
      (libsource (lib "eagle-import") (part "LM78L15"))
    )
    (comp (ref "U06B")
      (value "LM358-DGKR")
      (footprint "eagle-import:MSOP-8")
      (libsource (lib "eagle-import") (part "LM358-DGKR"))
    )
  )
  (nets
    (net (code "1") (name "+3V3") (class "Default")
      (node (ref "C01M") (pin "1") (pinfunction "1_1") (pintype "passive"))
      (node (ref "C01S") (pin "1") (pinfunction "1_1") (pintype "passive"))
      (node (ref "C02M") (pin "1") (pinfunction "1_1") (pintype "passive"))
      (node (ref "C05B") (pin "2") (pinfunction "2_2") (pintype "passive"))
      (node (ref "C06B") (pin "2") (pinfunction "2_2") (pintype "passive"))
      (node (ref "J01M") (pin "3") (pinfunction "3_3") (pintype "passive"))
      (node (ref "J01S") (pin "4") (pinfunction "VDD_4") (pintype "power_in"))
      (node (ref "J02M") (pin "6") (pinfunction "6_6") (pintype "bidirectional"))
      (node (ref "J06B") (pin "1") (pinfunction "1_1") (pintype "passive"))
      (node (ref "L01B") (pin "2") (pinfunction "2_2") (pintype "passive"))
      (node (ref "R08M") (pin "1") (pinfunction "1_1") (pintype "passive"))
      (node (ref "R09M") (pin "1") (pinfunction "1_1") (pintype "passive"))
      (node (ref "SW01M") (pin "1") (pinfunction "1_1") (pintype "passive"))
      (node (ref "U01M") (pin "18") (pinfunction "VCC_18") (pintype "power_in"))
      (node (ref "U02B") (pin "5") (pinfunction "VOUT_5") (pintype "bidirectional"))
      (node (ref "U02M") (pin "18") (pinfunction "VCC_18") (pintype "power_in"))
      (node (ref "U03M") (pin "#24") (pinfunction "3V3_#24") (pintype "power_in"))
      (node (ref "U03M") (pin "24") (pinfunction "3V3_24") (pintype "power_in"))
      (node (ref "U03M") (pin "@24") (pinfunction "3V3_@24") (pintype "power_in"))
    )
    (net (code "2") (name "+15V") (class "Default")
      (node (ref "C14B") (pin "2") (pinfunction "2_2") (pintype "passive"))
      (node (ref "C15B") (pin "2") (pinfunction "2_2") (pintype "passive"))
      (node (ref "J02S") (pin "2") (pinfunction "VPOS_2") (pintype "bidirectional"))
      (node (ref "J12B") (pin "1") (pinfunction "1_1") (pintype "passive"))
      (node (ref "U05B") (pin "1") (pinfunction "VOUT_1") (pintype "bidirectional"))
      (node (ref "U06B") (pin "8") (pinfunction "V+_8") (pintype "power_in"))
    )
    (net (code "3") (name "+22V") (class "Default")
      (node (ref "C10B") (pin "2") (pinfunction "2_2") (pintype "passive"))
      (node (ref "C13B") (pin "2") (pinfunction "2_2") (pintype "passive"))
      (node (ref "D05B") (pin "C") (pinfunction "C_C") (pintype "passive"))
      (node (ref "J02S") (pin "23") (pinfunction "GVDD_23") (pintype "bidirectional"))
      (node (ref "J10B") (pin "1") (pinfunction "1_1") (pintype "passive"))
      (node (ref "R15B") (pin "2") (pinfunction "2_2") (pintype "passive"))
      (node (ref "U05B") (pin "8") (pinfunction "VIN_8") (pintype "bidirectional"))
    )
    (net (code "4") (name "-15V") (class "Default")
      (node (ref "C12B") (pin "2") (pinfunction "2_2") (pintype "passive"))
      (node (ref "C16B") (pin "2") (pinfunction "2_2") (pintype "passive"))
      (node (ref "J02S") (pin "1") (pinfunction "VNEG_1") (pintype "bidirectional"))
      (node (ref "J11B") (pin "1") (pinfunction "1_1") (pintype "passive"))
      (node (ref "R17B") (pin "2") (pinfunction "2_2") (pintype "passive"))
      (node (ref "U04B") (pin "1") (pinfunction "VOUT_1") (pintype "bidirectional"))
      (node (ref "U06B") (pin "4") (pinfunction "V-_4") (pintype "power_in"))
    )
    (net (code "5") (name "-20V") (class "Default")
      (node (ref "C08B") (pin "2") (pinfunction "2_2") (pintype "passive"))
      (node (ref "C11B") (pin "2") (pinfunction "2_2") (pintype "passive"))
      (node (ref "D04B") (pin "A") (pinfunction "A_A") (pintype "passive"))
      (node (ref "J02S") (pin "24") (pinfunction "GVEE_24") (pintype "bidirectional"))
      (node (ref "J09B") (pin "1") (pinfunction "1_1") (pintype "passive"))
      (node (ref "R13B") (pin "2") (pinfunction "2_2") (pintype "passive"))
      (node (ref "U04B") (pin "2") (pinfunction "VIN_2") (pintype "bidirectional"))
      (node (ref "U04B") (pin "3") (pinfunction "VIN_3") (pintype "bidirectional"))
      (node (ref "U04B") (pin "6") (pinfunction "VIN_6") (pintype "bidirectional"))
      (node (ref "U04B") (pin "7") (pinfunction "VIN_7") (pintype "bidirectional"))
    )
    (net (code "6") (name "1") (class "Default")
      (node (ref "D02B") (pin "C") (pinfunction "C_C") (pintype "passive"))
      (node (ref "R19B") (pin "1") (pinfunction "1_1") (pintype "passive"))
      (node (ref "U01B") (pin "9") (pinfunction "~{CHG}_9") (pintype "bidirectional"))
    )
    (net (code "7") (name "BAT+") (class "Default")
      (node (ref "C20B") (pin "2") (pinfunction "2_2") (pintype "passive"))
      (node (ref "J03B") (pin "2") (pinfunction "+_2") (pintype "bidirectional"))
      (node (ref "J04B") (pin "1") (pinfunction "1_1") (pintype "passive"))
      (node (ref "R22B") (pin "1") (pinfunction "1_1") (pintype "passive"))
      (node (ref "U1") (pin "3") (pinfunction "VBAT_3") (pintype "power_in"))
    )
    (net (code "8") (name "BM_CE") (class "Default")
      (node (ref "R05B") (pin "2") (pinfunction "2_2") (pintype "passive"))
      (node (ref "U01B") (pin "4") (pinfunction "~{CE}_4") (pintype "bidirectional"))
    )
    (net (code "9") (name "BM_CHG") (class "Default")
      (node (ref "R19B") (pin "2") (pinfunction "2_2") (pintype "passive"))
      (node (ref "U03M") (pin "#12") (pinfunction "A0_#12") (pintype "bidirectional"))
      (node (ref "U03M") (pin "12") (pinfunction "A0_12") (pintype "bidirectional"))
      (node (ref "U03M") (pin "@12") (pinfunction "A0_@12") (pintype "bidirectional"))
    )
    (net (code "10") (name "BM_OUT") (class "Default")
      (node (ref "C03B") (pin "2") (pinfunction "2_2") (pintype "passive"))
      (node (ref "C04B") (pin "2") (pinfunction "2_2") (pintype "passive"))
      (node (ref "J02B") (pin "1") (pinfunction "1_1") (pintype "passive"))
      (node (ref "Q01B") (pin "2") (pinfunction "S_2") (pintype "passive"))
      (node (ref "R01B") (pin "1") (pinfunction "1_1") (pintype "passive"))
      (node (ref "R02B") (pin "2") (pinfunction "2_2") (pintype "passive"))
      (node (ref "R04B") (pin "2") (pinfunction "2_2") (pintype "passive"))
      (node (ref "R11B") (pin "2") (pinfunction "2_2") (pintype "passive"))
      (node (ref "R12B") (pin "2") (pinfunction "2_2") (pintype "passive"))
      (node (ref "R22B") (pin "2") (pinfunction "2_2") (pintype "passive"))
      (node (ref "U01B") (pin "10") (pinfunction "OUT_10") (pintype "bidirectional"))
      (node (ref "U01B") (pin "11") (pinfunction "OUT_11") (pintype "bidirectional"))
      (node (ref "U02B") (pin "4") (pinfunction "VIN_4") (pintype "bidirectional"))
    )
    (net (code "11") (name "BM_PGOOD") (class "Default")
      (node (ref "D01B") (pin "C") (pinfunction "C_C") (pintype "passive"))
      (node (ref "U01B") (pin "7") (pinfunction "~{PGOOD}_7") (pintype "bidirectional"))
      (node (ref "U03M") (pin "#6") (pinfunction "DAC_#6") (pintype "bidirectional"))
      (node (ref "U03M") (pin "6") (pinfunction "DAC_6") (pintype "bidirectional"))
      (node (ref "U03M") (pin "@6") (pinfunction "DAC_@6") (pintype "bidirectional"))
    )
    (net (code "12") (name "BM_SYSOFF") (class "Default")
      (node (ref "R07B") (pin "2") (pinfunction "2_2") (pintype "passive"))
      (node (ref "U01B") (pin "15") (pinfunction "SYSOFF_15") (pintype "bidirectional"))
    )
    (net (code "13") (name "CE2") (class "Default")
      (node (ref "J02S") (pin "10") (pinfunction "CE2_10") (pintype "bidirectional"))
      (node (ref "R03D") (pin "2") (pinfunction "2_2") (pintype "passive"))
    )
    (net (code "14") (name "CL") (class "Default")
      (node (ref "J02S") (pin "5") (pinfunction "CL_5") (pintype "bidirectional"))
      (node (ref "U02M") (pin "9") (pinfunction "GP0_9") (pintype "bidirectional"))
    )
    (net (code "15") (name "D0") (class "Default")
      (node (ref "J02S") (pin "12") (pinfunction "D0_12") (pintype "bidirectional"))
      (node (ref "U01M") (pin "9") (pinfunction "GP0_9") (pintype "bidirectional"))
    )
    (net (code "16") (name "D1") (class "Default")
      (node (ref "J02S") (pin "13") (pinfunction "D1_13") (pintype "bidirectional"))
      (node (ref "U01M") (pin "10") (pinfunction "GP1_10") (pintype "bidirectional"))
    )
    (net (code "17") (name "D2") (class "Default")
      (node (ref "J02S") (pin "14") (pinfunction "D2_14") (pintype "bidirectional"))
      (node (ref "U01M") (pin "11") (pinfunction "GP2_11") (pintype "bidirectional"))
    )
    (net (code "18") (name "D3") (class "Default")
      (node (ref "J02S") (pin "15") (pinfunction "D3_15") (pintype "bidirectional"))
      (node (ref "U01M") (pin "12") (pinfunction "GP3_12") (pintype "bidirectional"))
    )
    (net (code "19") (name "D4") (class "Default")
      (node (ref "J02S") (pin "16") (pinfunction "D4_16") (pintype "bidirectional"))
      (node (ref "U01M") (pin "13") (pinfunction "GP4_13") (pintype "bidirectional"))
    )
    (net (code "20") (name "D5") (class "Default")
      (node (ref "J02S") (pin "17") (pinfunction "D5_17") (pintype "bidirectional"))
      (node (ref "U01M") (pin "14") (pinfunction "GP5_14") (pintype "bidirectional"))
    )
    (net (code "21") (name "D6") (class "Default")
      (node (ref "J02S") (pin "18") (pinfunction "D6_18") (pintype "bidirectional"))
      (node (ref "U01M") (pin "15") (pinfunction "GP6_15") (pintype "bidirectional"))
    )
    (net (code "22") (name "D7") (class "Default")
      (node (ref "J02S") (pin "19") (pinfunction "D7_19") (pintype "bidirectional"))
      (node (ref "U01M") (pin "16") (pinfunction "GP7_16") (pintype "bidirectional"))
    )
    (net (code "23") (name "E_INK_VDD") (class "Default")
      (node (ref "J02S") (pin "4") (pinfunction "VDD_4") (pintype "bidirectional"))
      (node (ref "R01D") (pin "1") (pinfunction "1_1") (pintype "passive"))
      (node (ref "R04M") (pin "2") (pinfunction "2_2") (pintype "passive"))
      (node (ref "R05D") (pin "1") (pinfunction "1_1") (pintype "passive"))
      (node (ref "R08D") (pin "1") (pinfunction "1_1") (pintype "passive"))
      (node (ref "R09D") (pin "1") (pinfunction "1_1") (pintype "passive"))
      (node (ref "SJ1") (pin "3") (pinfunction "3_3") (pintype "passive"))
      (node (ref "U03M") (pin "#11") (pinfunction "A1_#11") (pintype "bidirectional"))
      (node (ref "U03M") (pin "11") (pinfunction "A1_11") (pintype "bidirectional"))
      (node (ref "U03M") (pin "@11") (pinfunction "A1_@11") (pintype "bidirectional"))
    )
    (net (code "24") (name "FB2") (class "Default")
      (node (ref "C10B") (pin "1") (pinfunction "1_1") (pintype "passive"))
      (node (ref "R15B") (pin "1") (pinfunction "1_1") (pintype "passive"))
      (node (ref "R16B") (pin "2") (pinfunction "2_2") (pintype "passive"))
      (node (ref "U03B") (pin "5") (pinfunction "FB2_5") (pintype "bidirectional"))
    )
    (net (code "25") (name "GMODE2") (class "Default")
      (node (ref "J02S") (pin "27") (pinfunction "GMODE2_27") (pintype "bidirectional"))
      (node (ref "R04D") (pin "1") (pinfunction "1_1") (pintype "passive"))
      (node (ref "U03M") (pin "#15") (pinfunction "D2_#15") (pintype "bidirectional"))
      (node (ref "U03M") (pin "15") (pinfunction "D2_15") (pintype "bidirectional"))
      (node (ref "U03M") (pin "@15") (pinfunction "D2_@15") (pintype "bidirectional"))
    )
    (net (code "26") (name "GND") (class "Default")
      (node (ref "C01B") (pin "1") (pinfunction "1_1") (pintype "passive"))
      (node (ref "C01M") (pin "2") (pinfunction "2_2") (pintype "passive"))
      (node (ref "C01S") (pin "2") (pinfunction "2_2") (pintype "passive"))
      (node (ref "C02B") (pin "1") (pinfunction "1_1") (pintype "passive"))
      (node (ref "C02M") (pin "2") (pinfunction "2_2") (pintype "passive"))
      (node (ref "C02S") (pin "2") (pinfunction "2_2") (pintype "passive"))
      (node (ref "C03B") (pin "1") (pinfunction "1_1") (pintype "passive"))
      (node (ref "C03S") (pin "2") (pinfunction "2_2") (pintype "passive"))
      (node (ref "C04B") (pin "1") (pinfunction "1_1") (pintype "passive"))
      (node (ref "C04S") (pin "2") (pinfunction "2_2") (pintype "passive"))
      (node (ref "C05B") (pin "1") (pinfunction "1_1") (pintype "passive"))
      (node (ref "C06B") (pin "1") (pinfunction "1_1") (pintype "passive"))
      (node (ref "C09B") (pin "1") (pinfunction "1_1") (pintype "passive"))
      (node (ref "C11B") (pin "1") (pinfunction "1_1") (pintype "passive"))
      (node (ref "C12B") (pin "1") (pinfunction "1_1") (pintype "passive"))
      (node (ref "C13B") (pin "1") (pinfunction "1_1") (pintype "passive"))
      (node (ref "C14B") (pin "1") (pinfunction "1_1") (pintype "passive"))
      (node (ref "C15B") (pin "1") (pinfunction "1_1") (pintype "passive"))
      (node (ref "C16B") (pin "1") (pinfunction "1_1") (pintype "passive"))
      (node (ref "C17B") (pin "1") (pinfunction "1_1") (pintype "passive"))
      (node (ref "C19B") (pin "1") (pinfunction "1_1") (pintype "passive"))
      (node (ref "C20B") (pin "1") (pinfunction "1_1") (pintype "passive"))
      (node (ref "D03B") (pin "C") (pinfunction "C_C") (pintype "passive"))
      (node (ref "J01M") (pin "1") (pinfunction "1_1") (pintype "passive"))
      (node (ref "J01S") (pin "6") (pinfunction "VSS_6") (pintype "power_in"))
      (node (ref "J01S") (pin "MT1") (pinfunction "GND_MT1") (pintype "power_in"))
      (node (ref "J01S") (pin "MT2") (pinfunction "GND1_MT2") (pintype "power_in"))
      (node (ref "J02M") (pin "2") (pinfunction "2_2") (pintype "bidirectional"))
      (node (ref "J02S") (pin "3") (pinfunction "VSS_3") (pintype "bidirectional"))
      (node (ref "J03B") (pin "1") (pinfunction "-_1") (pintype "bidirectional"))
      (node (ref "J03M") (pin "2") (pinfunction "-_2") (pintype "power_in"))
      (node (ref "J07B") (pin "GND") (pinfunction "GND_GND") (pintype "bidirectional"))
      (node (ref "J07B") (pin "MT1") (pinfunction "GND_MT1") (pintype "bidirectional"))
      (node (ref "J07B") (pin "MT2") (pinfunction "GND_MT2") (pintype "bidirectional"))
      (node (ref "R01M") (pin "2") (pinfunction "2_2") (pintype "passive"))
      (node (ref "R02D") (pin "2") (pinfunction "2_2") (pintype "passive"))
      (node (ref "R02M") (pin "2") (pinfunction "2_2") (pintype "passive"))
      (node (ref "R03B") (pin "2") (pinfunction "2_2") (pintype "passive"))
      (node (ref "R03M") (pin "2") (pinfunction "2_2") (pintype "passive"))
      (node (ref "R05B") (pin "1") (pinfunction "1_1") (pintype "passive"))
      (node (ref "R05M") (pin "2") (pinfunction "2_2") (pintype "passive"))
      (node (ref "R06B") (pin "1") (pinfunction "1_1") (pintype "passive"))
      (node (ref "R06D") (pin "1") (pinfunction "1_1") (pintype "passive"))
      (node (ref "R06M") (pin "2") (pinfunction "2_2") (pintype "passive"))
      (node (ref "R07B") (pin "1") (pinfunction "1_1") (pintype "passive"))
      (node (ref "R07D") (pin "2") (pinfunction "2_2") (pintype "passive"))
      (node (ref "R08B") (pin "1") (pinfunction "1_1") (pintype "passive"))
      (node (ref "R09B") (pin "1") (pinfunction "1_1") (pintype "passive"))
      (node (ref "R10B") (pin "1") (pinfunction "1_1") (pintype "passive"))
      (node (ref "R14B") (pin "1") (pinfunction "1_1") (pintype "passive"))
      (node (ref "R16B") (pin "1") (pinfunction "1_1") (pintype "passive"))
      (node (ref "R18B") (pin "1") (pinfunction "A_1") (pintype "passive"))
      (node (ref "R21B") (pin "1") (pinfunction "1_1") (pintype "passive"))
      (node (ref "SJ1") (pin "1") (pinfunction "1_1") (pintype "passive"))
      (node (ref "U01B") (pin "8") (pinfunction "VSS_8") (pintype "bidirectional"))
      (node (ref "U01M") (pin "17") (pinfunction "GND_17") (pintype "power_in"))
      (node (ref "U01S") (pin "12") (pinfunction "SDO_12") (pintype "bidirectional"))
      (node (ref "U01S") (pin "2") (pinfunction "GND_2") (pintype "bidirectional"))
      (node (ref "U01S") (pin "4") (pinfunction "GND_4") (pintype "bidirectional"))
      (node (ref "U01S") (pin "5") (pinfunction "GND_5") (pintype "bidirectional"))
      (node (ref "U02B") (pin "2") (pinfunction "GND_2") (pintype "bidirectional"))
      (node (ref "U02M") (pin "17") (pinfunction "GND_17") (pintype "power_in"))
      (node (ref "U03B") (pin "3") (pinfunction "GND_3") (pintype "bidirectional"))
      (node (ref "U03B") (pin "7") (pinfunction "PGND_7") (pintype "bidirectional"))
      (node (ref "U03B") (pin "9") (pinfunction "PGND_9") (pintype "bidirectional"))
      (node (ref "U03M") (pin "#2") (pinfunction "GND_#2") (pintype "power_in"))
      (node (ref "U03M") (pin "#21") (pinfunction "GND_#21") (pintype "power_in"))
      (node (ref "U03M") (pin "2") (pinfunction "GND_2") (pintype "power_in"))
      (node (ref "U03M") (pin "21") (pinfunction "GND_21") (pintype "power_in"))
      (node (ref "U03M") (pin "@2") (pinfunction "GND_@2") (pintype "power_in"))
      (node (ref "U03M") (pin "@21") (pinfunction "GND_@21") (pintype "power_in"))
      (node (ref "U04B") (pin "5") (pinfunction "GND_5") (pintype "bidirectional"))
      (node (ref "U05B") (pin "2") (pinfunction "GND_2") (pintype "bidirectional"))
      (node (ref "U05B") (pin "3") (pinfunction "GND_3") (pintype "bidirectional"))
      (node (ref "U05B") (pin "6") (pinfunction "GND_6") (pintype "bidirectional"))
      (node (ref "U05B") (pin "7") (pinfunction "GND_7") (pintype "bidirectional"))
      (node (ref "U1") (pin "2") (pinfunction "VSS_2") (pintype "power_in"))
    )
    (net (code "27") (name "JTAG_TCK") (class "Default")
      (node (ref "J02M") (pin "3") (pinfunction "3_3") (pintype "bidirectional"))
      (node (ref "U03M") (pin "#19") (pinfunction "D6_#19") (pintype "bidirectional"))
      (node (ref "U03M") (pin "19") (pinfunction "D6_19") (pintype "bidirectional"))
      (node (ref "U03M") (pin "@19") (pinfunction "D6_@19") (pintype "bidirectional"))
    )
    (net (code "28") (name "JTAG_TMS") (class "Default")
      (node (ref "J02M") (pin "1") (pinfunction "1_1") (pintype "bidirectional"))
      (node (ref "U03M") (pin "#20") (pinfunction "D7_#20") (pintype "bidirectional"))
      (node (ref "U03M") (pin "20") (pinfunction "D7_20") (pintype "bidirectional"))
      (node (ref "U03M") (pin "@20") (pinfunction "D7_@20") (pintype "bidirectional"))
    )
    (net (code "29") (name "JTAG_TRST") (class "Default")
      (node (ref "J02M") (pin "5") (pinfunction "5_5") (pintype "bidirectional"))
      (node (ref "R02S") (pin "1") (pinfunction "1_1") (pintype "passive"))
      (node (ref "U03M") (pin "#16") (pinfunction "D3_#16") (pintype "bidirectional"))
      (node (ref "U03M") (pin "16") (pinfunction "D3_16") (pintype "bidirectional"))
      (node (ref "U03M") (pin "@16") (pinfunction "D3_@16") (pintype "bidirectional"))
    )
    (net (code "30") (name "LE") (class "Default")
      (node (ref "J02S") (pin "6") (pinfunction "LE_6") (pintype "bidirectional"))
      (node (ref "U02M") (pin "10") (pinfunction "GP1_10") (pintype "bidirectional"))
    )
    (net (code "31") (name "MCU_RST") (class "Default")
      (node (ref "J02M") (pin "4") (pinfunction "4_4") (pintype "bidirectional"))
      (node (ref "U03M") (pin "#23") (pinfunction "~{RST}_#23") (pintype "bidirectional"))
      (node (ref "U03M") (pin "23") (pinfunction "~{RST}_23") (pintype "bidirectional"))
      (node (ref "U03M") (pin "@23") (pinfunction "~{RST}_@23") (pintype "bidirectional"))
    )
    (net (code "32") (name "MCU_RX") (class "Default")
      (node (ref "J01M") (pin "4") (pinfunction "4_4") (pintype "passive"))
      (node (ref "U03M") (pin "#4") (pinfunction "RX_#4") (pintype "bidirectional"))
      (node (ref "U03M") (pin "4") (pinfunction "RX_4") (pintype "bidirectional"))
      (node (ref "U03M") (pin "@4") (pinfunction "RX_@4") (pintype "bidirectional"))
    )
    (net (code "33") (name "MCU_TX") (class "Default")
      (node (ref "J01M") (pin "5") (pinfunction "5_5") (pintype "passive"))
      (node (ref "U03M") (pin "#3") (pinfunction "TX_#3") (pintype "bidirectional"))
      (node (ref "U03M") (pin "3") (pinfunction "TX_3") (pintype "bidirectional"))
      (node (ref "U03M") (pin "@3") (pinfunction "TX_@3") (pintype "bidirectional"))
    )
    (net (code "34") (name "MCU_USB_DM") (class "Default")
      (node (ref "J07B") (pin "D-") (pinfunction "D-_D-") (pintype "bidirectional"))
    )
    (net (code "35") (name "MCU_USB_DP") (class "Default")
      (node (ref "J07B") (pin "D+") (pinfunction "D+_D+") (pintype "bidirectional"))
    )
    (net (code "36") (name "MCU_VBAT") (class "Default")
      (node (ref "J03M") (pin "1") (pinfunction "+_1") (pintype "power_in"))
      (node (ref "U03M") (pin "#22") (pinfunction "VBAT_#22") (pintype "power_in"))
      (node (ref "U03M") (pin "22") (pinfunction "VBAT_22") (pintype "power_in"))
      (node (ref "U03M") (pin "@22") (pinfunction "VBAT_@22") (pintype "power_in"))
    )
    (net (code "37") (name "MCU_VIN") (class "Default")
      (node (ref "U03M") (pin "#1") (pinfunction "VIN_#1") (pintype "power_in"))
      (node (ref "U03M") (pin "1") (pinfunction "VIN_1") (pintype "power_in"))
      (node (ref "U03M") (pin "@1") (pinfunction "VIN_@1") (pintype "power_in"))
    )
    (net (code "38") (name "MCU_WKP") (class "Default")
      (node (ref "SW01M") (pin "3") (pinfunction "2_3") (pintype "passive"))
      (node (ref "U03M") (pin "#5") (pinfunction "WKP_#5") (pintype "bidirectional"))
      (node (ref "U03M") (pin "5") (pinfunction "WKP_5") (pintype "bidirectional"))
      (node (ref "U03M") (pin "@5") (pinfunction "WKP_@5") (pintype "bidirectional"))
    )
    (net (code "39") (name "N$31") (class "Default")
      (node (ref "U02M") (pin "14") (pinfunction "GP5_14") (pintype "bidirectional"))
    )
    (net (code "40") (name "NEG_EN") (class "Default")
      (node (ref "U02M") (pin "13") (pinfunction "GP4_13") (pintype "bidirectional"))
      (node (ref "U03B") (pin "2") (pinfunction "~{SHDN1}_2") (pintype "bidirectional"))
    )
    (net (code "41") (name "NFB1") (class "Default")
      (node (ref "C08B") (pin "1") (pinfunction "1_1") (pintype "passive"))
      (node (ref "R13B") (pin "1") (pinfunction "1_1") (pintype "passive"))
      (node (ref "R14B") (pin "2") (pinfunction "2_2") (pintype "passive"))
      (node (ref "U03B") (pin "1") (pinfunction "NFB1_1") (pintype "bidirectional"))
    )
    (net (code "42") (name "Net-(C02B-Pad2)") (class "Default")
      (node (ref "C02B") (pin "2") (pinfunction "2_2") (pintype "passive"))
      (node (ref "J04B") (pin "2") (pinfunction "2_2") (pintype "passive"))
      (node (ref "J05B") (pin "1") (pinfunction "1_1") (pintype "passive"))
      (node (ref "U01B") (pin "2") (pinfunction "BAT_2") (pintype "bidirectional"))
      (node (ref "U01B") (pin "3") (pinfunction "BAT_3") (pintype "bidirectional"))
    )
    (net (code "43") (name "Net-(C07B-Pad2)") (class "Default")
      (node (ref "C07B") (pin "2") (pinfunction "2_2") (pintype "passive"))
      (node (ref "D03B") (pin "A") (pinfunction "A_A") (pintype "passive"))
      (node (ref "D04B") (pin "C") (pinfunction "C_C") (pintype "passive"))
    )
    (net (code "44") (name "Net-(D01B-PadA)") (class "Default")
      (node (ref "D01B") (pin "A") (pinfunction "A_A") (pintype "passive"))
      (node (ref "R01B") (pin "2") (pinfunction "2_2") (pintype "passive"))
    )
    (net (code "45") (name "Net-(D01S-PadA)") (class "Default")
      (node (ref "D01S") (pin "A") (pinfunction "A_A") (pintype "passive"))
      (node (ref "R01S") (pin "1") (pinfunction "1_1") (pintype "passive"))
    )
    (net (code "46") (name "Net-(D02B-PadA)") (class "Default")
      (node (ref "D02B") (pin "A") (pinfunction "A_A") (pintype "passive"))
      (node (ref "R02B") (pin "1") (pinfunction "1_1") (pintype "passive"))
    )
    (net (code "47") (name "Net-(D06B-PadA)") (class "Default")
      (node (ref "D06B") (pin "A") (pinfunction "A_A") (pintype "passive"))
      (node (ref "R20B") (pin "2") (pinfunction "2_2") (pintype "passive"))
    )
    (net (code "48") (name "Net-(J02S-CE1)") (class "Default")
      (node (ref "J02S") (pin "9") (pinfunction "CE1_9") (pintype "bidirectional"))
      (node (ref "R02D") (pin "1") (pinfunction "1_1") (pintype "passive"))
    )
    (net (code "49") (name "Net-(J02S-GMODE1)") (class "Default")
      (node (ref "J02S") (pin "28") (pinfunction "GMODE1_28") (pintype "bidirectional"))
      (node (ref "R04D") (pin "2") (pinfunction "2_2") (pintype "passive"))
    )
    (net (code "50") (name "Net-(J02S-RL)") (class "Default")
      (node (ref "J02S") (pin "29") (pinfunction "RL_29") (pintype "bidirectional"))
      (node (ref "SJ1") (pin "2") (pinfunction "2_2") (pintype "passive"))
    )
    (net (code "51") (name "Net-(J02S-U1CE1)") (class "Default")
      (node (ref "J02S") (pin "31") (pinfunction "U1CE1_31") (pintype "bidirectional"))
      (node (ref "R06D") (pin "2") (pinfunction "2_2") (pintype "passive"))
    )
    (net (code "52") (name "Net-(J02S-U1CE2)") (class "Default")
      (node (ref "J02S") (pin "30") (pinfunction "U1CE2_30") (pintype "bidirectional"))
      (node (ref "R05D") (pin "2") (pinfunction "2_2") (pintype "passive"))
    )
    (net (code "53") (name "Net-(J02S-U2CE1)") (class "Default")
      (node (ref "J02S") (pin "36") (pinfunction "U2CE1_36") (pintype "bidirectional"))
      (node (ref "R09D") (pin "2") (pinfunction "2_2") (pintype "passive"))
    )
    (net (code "54") (name "Net-(J02S-U2CE2)") (class "Default")
      (node (ref "J02S") (pin "35") (pinfunction "U2CE2_35") (pintype "bidirectional"))
      (node (ref "R08D") (pin "2") (pinfunction "2_2") (pintype "passive"))
    )
    (net (code "55") (name "Net-(J02S-U2CKV)") (class "Default")
      (node (ref "J02S") (pin "38") (pinfunction "U2CKV_38") (pintype "bidirectional"))
      (node (ref "R10D") (pin "1") (pinfunction "1_1") (pintype "passive"))
    )
    (net (code "56") (name "Net-(J02S-U2SPV)") (class "Default")
      (node (ref "J02S") (pin "37") (pinfunction "U2SPV_37") (pintype "bidirectional"))
      (node (ref "R11D") (pin "1") (pinfunction "1_1") (pintype "passive"))
    )
    (net (code "57") (name "Net-(J02S-VBORDER)") (class "Default")
      (node (ref "J02S") (pin "34") (pinfunction "VBORDER_34") (pintype "bidirectional"))
      (node (ref "R07D") (pin "1") (pinfunction "1_1") (pintype "passive"))
    )
    (net (code "58") (name "Net-(R18B-E)") (class "Default")
      (node (ref "R17B") (pin "1") (pinfunction "1_1") (pintype "passive"))
      (node (ref "R18B") (pin "3") (pinfunction "E_3") (pintype "passive"))
    )
    (net (code "59") (name "Net-(R18B-S)") (class "Default")
      (node (ref "R18B") (pin "2") (pinfunction "S_2") (pintype "passive"))
      (node (ref "U06B") (pin "5") (pinfunction "+IN2_5") (pintype "input"))
    )
    (net (code "60") (name "Net-(TP01B-TP)") (class "Default")
      (node (ref "R11B") (pin "1") (pinfunction "1_1") (pintype "passive"))
      (node (ref "TP01B") (pin "P$1") (pinfunction "TP_P$1") (pintype "bidirectional"))
      (node (ref "U02B") (pin "1") (pinfunction "EN_1") (pintype "bidirectional"))
    )
    (net (code "61") (name "Net-(U$1-TP)") (class "Default")
      (node (ref "U$1") (pin "P$1") (pinfunction "TP_P$1") (pintype "bidirectional"))
      (node (ref "U01M") (pin "4") (pinfunction "/RST_4") (pintype "input"))
    )
    (net (code "62") (name "Net-(U$2-TP)") (class "Default")
      (node (ref "U$2") (pin "P$1") (pinfunction "TP_P$1") (pintype "bidirectional"))
      (node (ref "U01M") (pin "7") (pinfunction "INT_7") (pintype "output"))
    )
    (net (code "63") (name "Net-(U$3-TP)") (class "Default")
      (node (ref "U$3") (pin "P$1") (pinfunction "TP_P$1") (pintype "bidirectional"))
      (node (ref "U02M") (pin "4") (pinfunction "/RST_4") (pintype "input"))
    )
    (net (code "64") (name "Net-(U$4-TP)") (class "Default")
      (node (ref "U$4") (pin "P$1") (pinfunction "TP_P$1") (pintype "bidirectional"))
      (node (ref "U02M") (pin "7") (pinfunction "INT_7") (pintype "output"))
    )
    (net (code "65") (name "Net-(U1-PROG)") (class "Default")
      (node (ref "R21B") (pin "2") (pinfunction "2_2") (pintype "passive"))
      (node (ref "U1") (pin "5") (pinfunction "PROG_5") (pintype "input"))
    )
    (net (code "66") (name "Net-(U1-STAT)") (class "Default")
      (node (ref "D06B") (pin "C") (pinfunction "C_C") (pintype "passive"))
      (node (ref "U1") (pin "1") (pinfunction "STAT_1") (pintype "output"))
    )
    (net (code "67") (name "Net-(U01B-EN1)") (class "Default")
      (node (ref "R03B") (pin "1") (pinfunction "1_1") (pintype "passive"))
      (node (ref "U01B") (pin "6") (pinfunction "EN1_6") (pintype "bidirectional"))
    )
    (net (code "68") (name "Net-(U01B-EN2)") (class "Default")
      (node (ref "R04B") (pin "1") (pinfunction "1_1") (pintype "passive"))
      (node (ref "U01B") (pin "5") (pinfunction "EN2_5") (pintype "bidirectional"))
    )
    (net (code "69") (name "Net-(U01B-ILIM)") (class "Default")
      (node (ref "R08B") (pin "2") (pinfunction "2_2") (pintype "passive"))
      (node (ref "U01B") (pin "12") (pinfunction "ILIM_12") (pintype "bidirectional"))
    )
    (net (code "70") (name "Net-(U01B-ISET)") (class "Default")
      (node (ref "R09B") (pin "2") (pinfunction "2_2") (pintype "passive"))
      (node (ref "U01B") (pin "16") (pinfunction "ISET_16") (pintype "bidirectional"))
    )
    (net (code "71") (name "Net-(U01B-TMR)") (class "Default")
      (node (ref "R06B") (pin "2") (pinfunction "2_2") (pintype "passive"))
      (node (ref "U01B") (pin "14") (pinfunction "TMR_14") (pintype "bidirectional"))
    )
    (net (code "72") (name "Net-(U01B-TS)") (class "Default")
      (node (ref "R10B") (pin "2") (pinfunction "2_2") (pintype "passive"))
      (node (ref "U01B") (pin "1") (pinfunction "TS_1") (pintype "bidirectional"))
    )
    (net (code "73") (name "Net-(U01M-A0)") (class "Default")
      (node (ref "R01M") (pin "1") (pinfunction "1_1") (pintype "passive"))
      (node (ref "U01M") (pin "3") (pinfunction "A0_3") (pintype "input"))
    )
    (net (code "74") (name "Net-(U01M-A1)") (class "Default")
      (node (ref "R02M") (pin "1") (pinfunction "1_1") (pintype "passive"))
      (node (ref "U01M") (pin "2") (pinfunction "A1_2") (pintype "input"))
    )
    (net (code "75") (name "Net-(U01M-A2)") (class "Default")
      (node (ref "R03M") (pin "1") (pinfunction "1_1") (pintype "passive"))
      (node (ref "U01M") (pin "1") (pinfunction "A2_1") (pintype "input"))
    )
    (net (code "76") (name "Net-(U01S-CS)") (class "Default")
      (node (ref "C02S") (pin "1") (pinfunction "1_1") (pintype "passive"))
      (node (ref "C03S") (pin "1") (pinfunction "1_1") (pintype "passive"))
      (node (ref "C04S") (pin "1") (pinfunction "1_1") (pintype "passive"))
      (node (ref "U01S") (pin "1") (pinfunction "VDD_1") (pintype "bidirectional"))
      (node (ref "U01S") (pin "6") (pinfunction "VS_6") (pintype "bidirectional"))
      (node (ref "U01S") (pin "7") (pinfunction "CS_7") (pintype "bidirectional"))
    )
    (net (code "77") (name "Net-(U01S-INT1)") (class "Default")
      (node (ref "R02S") (pin "2") (pinfunction "2_2") (pintype "passive"))
      (node (ref "U01S") (pin "8") (pinfunction "INT1_8") (pintype "bidirectional"))
    )
    (net (code "78") (name "Net-(U02B-LX)") (class "Default")
      (node (ref "L01B") (pin "1") (pinfunction "1_1") (pintype "passive"))
      (node (ref "U02B") (pin "3") (pinfunction "LX_3") (pintype "bidirectional"))
    )
    (net (code "79") (name "Net-(U02M-A0)") (class "Default")
      (node (ref "R04M") (pin "1") (pinfunction "1_1") (pintype "passive"))
      (node (ref "U02M") (pin "3") (pinfunction "A0_3") (pintype "input"))
    )
    (net (code "80") (name "Net-(U02M-A1)") (class "Default")
      (node (ref "R05M") (pin "1") (pinfunction "1_1") (pintype "passive"))
      (node (ref "U02M") (pin "2") (pinfunction "A1_2") (pintype "input"))
    )
    (net (code "81") (name "Net-(U02M-A2)") (class "Default")
      (node (ref "R06M") (pin "1") (pinfunction "1_1") (pintype "passive"))
      (node (ref "U02M") (pin "1") (pinfunction "A2_1") (pintype "input"))
    )
    (net (code "82") (name "Net-(U03B-SW1)") (class "Default")
      (node (ref "C07B") (pin "1") (pinfunction "1_1") (pintype "passive"))
      (node (ref "L02B") (pin "P$2") (pinfunction "P$2_P$2") (pintype "bidirectional"))
      (node (ref "U03B") (pin "10") (pinfunction "SW1_10") (pintype "bidirectional"))
    )
    (net (code "83") (name "Net-(U03B-SW2)") (class "Default")
      (node (ref "D05B") (pin "A") (pinfunction "A_A") (pintype "passive"))
      (node (ref "L03B") (pin "P$2") (pinfunction "P$2_P$2") (pintype "bidirectional"))
      (node (ref "U03B") (pin "6") (pinfunction "SW2_6") (pintype "bidirectional"))
    )
    (net (code "84") (name "OE") (class "Default")
      (node (ref "J02S") (pin "7") (pinfunction "OE_7") (pintype "bidirectional"))
      (node (ref "U02M") (pin "11") (pinfunction "GP2_11") (pintype "bidirectional"))
    )
    (net (code "85") (name "POS_EN") (class "Default")
      (node (ref "U02M") (pin "16") (pinfunction "GP7_16") (pintype "bidirectional"))
      (node (ref "U03B") (pin "4") (pinfunction "~{SHDN2}_4") (pintype "bidirectional"))
    )
    (net (code "86") (name "SCL") (class "Default")
      (node (ref "R08M") (pin "2") (pinfunction "2_2") (pintype "passive"))
      (node (ref "U01M") (pin "19") (pinfunction "SCL_19") (pintype "bidirectional"))
      (node (ref "U01S") (pin "14") (pinfunction "SCL_14") (pintype "bidirectional"))
      (node (ref "U02M") (pin "19") (pinfunction "SCL_19") (pintype "bidirectional"))
      (node (ref "U03M") (pin "#14") (pinfunction "D1_#14") (pintype "bidirectional"))
      (node (ref "U03M") (pin "14") (pinfunction "D1_14") (pintype "bidirectional"))
      (node (ref "U03M") (pin "@14") (pinfunction "D1_@14") (pintype "bidirectional"))
    )
    (net (code "87") (name "SDA") (class "Default")
      (node (ref "R09M") (pin "2") (pinfunction "2_2") (pintype "passive"))
      (node (ref "U01M") (pin "20") (pinfunction "SDA_20") (pintype "bidirectional"))
      (node (ref "U01S") (pin "13") (pinfunction "SDA_13") (pintype "bidirectional"))
      (node (ref "U02M") (pin "20") (pinfunction "SDA_20") (pintype "bidirectional"))
      (node (ref "U03M") (pin "#13") (pinfunction "D0_#13") (pintype "bidirectional"))
      (node (ref "U03M") (pin "13") (pinfunction "D0_13") (pintype "bidirectional"))
      (node (ref "U03M") (pin "@13") (pinfunction "D0_@13") (pintype "bidirectional"))
    )
    (net (code "88") (name "SD_CD") (class "Default")
      (node (ref "J01S") (pin "CD1") (pinfunction "CARD_DETECT_CD1") (pintype "passive"))
      (node (ref "U$5") (pin "P$1") (pinfunction "TP_P$1") (pintype "bidirectional"))
    )
    (net (code "89") (name "SHR") (class "Default")
      (node (ref "J02S") (pin "8") (pinfunction "SHR_8") (pintype "bidirectional"))
      (node (ref "R01D") (pin "2") (pinfunction "2_2") (pintype "passive"))
      (node (ref "R03D") (pin "1") (pinfunction "1_1") (pintype "passive"))
    )
    (net (code "90") (name "SMPS_CTRL") (class "Default")
      (node (ref "Q01B") (pin "1") (pinfunction "G_1") (pintype "passive"))
      (node (ref "R12B") (pin "1") (pinfunction "1_1") (pintype "passive"))
      (node (ref "U02M") (pin "15") (pinfunction "GP6_15") (pintype "bidirectional"))
    )
    (net (code "91") (name "SPH") (class "Default")
      (node (ref "J02S") (pin "11") (pinfunction "SPH_11") (pintype "bidirectional"))
      (node (ref "U02M") (pin "12") (pinfunction "GP3_12") (pintype "bidirectional"))
    )
    (net (code "92") (name "SPI_CS") (class "Default")
      (node (ref "D01S") (pin "C") (pinfunction "C_C") (pintype "passive"))
      (node (ref "J01S") (pin "2") (pinfunction "CS_2") (pintype "input"))
      (node (ref "U03M") (pin "#10") (pinfunction "A2_#10") (pintype "bidirectional"))
      (node (ref "U03M") (pin "10") (pinfunction "A2_10") (pintype "bidirectional"))
      (node (ref "U03M") (pin "@10") (pinfunction "A2_@10") (pintype "bidirectional"))
    )
    (net (code "93") (name "SPI_MISO") (class "Default")
      (node (ref "J01S") (pin "7") (pinfunction "DATA_OUT_7") (pintype "output"))
      (node (ref "U03M") (pin "#8") (pinfunction "A4_#8") (pintype "bidirectional"))
      (node (ref "U03M") (pin "8") (pinfunction "A4_8") (pintype "bidirectional"))
      (node (ref "U03M") (pin "@8") (pinfunction "A4_@8") (pintype "bidirectional"))
    )
    (net (code "94") (name "SPI_MOSI") (class "Default")
      (node (ref "J01S") (pin "3") (pinfunction "DATA_IN_3") (pintype "input"))
      (node (ref "U03M") (pin "#7") (pinfunction "A5_#7") (pintype "bidirectional"))
      (node (ref "U03M") (pin "7") (pinfunction "A5_7") (pintype "bidirectional"))
      (node (ref "U03M") (pin "@7") (pinfunction "A5_@7") (pintype "bidirectional"))
    )
    (net (code "95") (name "SPI_SCK") (class "Default")
      (node (ref "J01S") (pin "5") (pinfunction "SCLK_5") (pintype "input"))
      (node (ref "R01S") (pin "2") (pinfunction "2_2") (pintype "passive"))
      (node (ref "U03M") (pin "#9") (pinfunction "A3_#9") (pintype "bidirectional"))
      (node (ref "U03M") (pin "9") (pinfunction "A3_9") (pintype "bidirectional"))
      (node (ref "U03M") (pin "@9") (pinfunction "A3_@9") (pintype "bidirectional"))
    )
    (net (code "96") (name "U1CKV") (class "Default")
      (node (ref "J02S") (pin "33") (pinfunction "U1CKV_33") (pintype "bidirectional"))
      (node (ref "R10D") (pin "2") (pinfunction "2_2") (pintype "passive"))
      (node (ref "U03M") (pin "#18") (pinfunction "D5_#18") (pintype "bidirectional"))
      (node (ref "U03M") (pin "18") (pinfunction "D5_18") (pintype "bidirectional"))
      (node (ref "U03M") (pin "@18") (pinfunction "D5_@18") (pintype "bidirectional"))
    )
    (net (code "97") (name "U1SPV") (class "Default")
      (node (ref "J02S") (pin "32") (pinfunction "U1SPV_32") (pintype "bidirectional"))
      (node (ref "R11D") (pin "2") (pinfunction "2_2") (pintype "passive"))
      (node (ref "U03M") (pin "#17") (pinfunction "D4_#17") (pintype "bidirectional"))
      (node (ref "U03M") (pin "17") (pinfunction "D4_17") (pintype "bidirectional"))
      (node (ref "U03M") (pin "@17") (pinfunction "D4_@17") (pintype "bidirectional"))
    )
    (net (code "98") (name "VBUS") (class "Default")
      (node (ref "C01B") (pin "2") (pinfunction "2_2") (pintype "passive"))
      (node (ref "C19B") (pin "2") (pinfunction "2_2") (pintype "passive"))
      (node (ref "J01B") (pin "1") (pinfunction "1_1") (pintype "passive"))
      (node (ref "J07B") (pin "VBUS") (pinfunction "VBUS_VBUS") (pintype "bidirectional"))
      (node (ref "R20B") (pin "1") (pinfunction "1_1") (pintype "passive"))
      (node (ref "U01B") (pin "13") (pinfunction "IN_13") (pintype "bidirectional"))
      (node (ref "U1") (pin "4") (pinfunction "VIN_4") (pintype "power_in"))
    )
    (net (code "99") (name "VCOM") (class "Default")
      (node (ref "C17B") (pin "2") (pinfunction "2_2") (pintype "passive"))
      (node (ref "J02S") (pin "22") (pinfunction "VCOM_22") (pintype "bidirectional"))
      (node (ref "J13B") (pin "1") (pinfunction "1_1") (pintype "passive"))
      (node (ref "U06B") (pin "6") (pinfunction "-IN2_6") (pintype "input"))
      (node (ref "U06B") (pin "7") (pinfunction "OUT2_7") (pintype "output"))
    )
    (net (code "100") (name "VIN") (class "Default")
      (node (ref "C09B") (pin "2") (pinfunction "2_2") (pintype "passive"))
      (node (ref "J08B") (pin "1") (pinfunction "1_1") (pintype "passive"))
      (node (ref "L02B") (pin "P$1") (pinfunction "P$1_P$1") (pintype "bidirectional"))
      (node (ref "L03B") (pin "P$1") (pinfunction "P$1_P$1") (pintype "bidirectional"))
      (node (ref "Q01B") (pin "3") (pinfunction "D_3") (pintype "passive"))
      (node (ref "U03B") (pin "8") (pinfunction "VIN_8") (pintype "bidirectional"))
    )
    (net (code "101") (name "unconnected-(J01M-Pad2)") (class "Default")
      (node (ref "J01M") (pin "2") (pinfunction "2_2") (pintype "passive"))
    )
    (net (code "102") (name "unconnected-(J01S-CARD_DETECT1-PadCD2)") (class "Default")
      (node (ref "J01S") (pin "CD2") (pinfunction "CARD_DETECT1_CD2") (pintype "passive"))
    )
    (net (code "103") (name "unconnected-(J01S-DAT1-Pad8)") (class "Default")
      (node (ref "J01S") (pin "8") (pinfunction "DAT1_8") (pintype "bidirectional"))
    )
    (net (code "104") (name "unconnected-(J01S-DAT2-Pad1)") (class "Default")
      (node (ref "J01S") (pin "1") (pinfunction "DAT2_1") (pintype "bidirectional"))
    )
    (net (code "105") (name "unconnected-(J02S-NC-20-Pad20)") (class "Default")
      (node (ref "J02S") (pin "20") (pinfunction "NC-20_20") (pintype "bidirectional"))
    )
    (net (code "106") (name "unconnected-(J02S-NC-21-Pad21)") (class "Default")
      (node (ref "J02S") (pin "21") (pinfunction "NC-21_21") (pintype "bidirectional"))
    )
    (net (code "107") (name "unconnected-(J02S-NC-25-Pad25)") (class "Default")
      (node (ref "J02S") (pin "25") (pinfunction "NC-25_25") (pintype "bidirectional"))
    )
    (net (code "108") (name "unconnected-(J02S-NC-26-Pad26)") (class "Default")
      (node (ref "J02S") (pin "26") (pinfunction "NC-26_26") (pintype "bidirectional"))
    )
    (net (code "109") (name "unconnected-(J02S-NC-39-Pad39)") (class "Default")
      (node (ref "J02S") (pin "39") (pinfunction "NC-39_39") (pintype "bidirectional"))
    )
    (net (code "110") (name "unconnected-(J03B-PAD1-PadNC1)") (class "Default")
      (node (ref "J03B") (pin "NC1") (pinfunction "PAD1_NC1") (pintype "bidirectional"))
    )
    (net (code "111") (name "unconnected-(J03B-PAD2-PadNC2)") (class "Default")
      (node (ref "J03B") (pin "NC2") (pinfunction "PAD2_NC2") (pintype "bidirectional"))
    )
    (net (code "112") (name "unconnected-(U01S-INT2-Pad9)") (class "Default")
      (node (ref "U01S") (pin "9") (pinfunction "INT2_9") (pintype "bidirectional"))
    )
    (net (code "113") (name "unconnected-(U01S-NC-Pad3)") (class "Default")
      (node (ref "U01S") (pin "3") (pinfunction "NC_3") (pintype "bidirectional"))
    )
    (net (code "114") (name "unconnected-(U01S-NC-Pad10)") (class "Default")
      (node (ref "U01S") (pin "10") (pinfunction "NC_10") (pintype "bidirectional"))
    )
    (net (code "115") (name "unconnected-(U01S-NC-Pad11)") (class "Default")
      (node (ref "U01S") (pin "11") (pinfunction "NC_11") (pintype "bidirectional"))
    )
    (net (code "116") (name "unconnected-(U04B-NC-Pad4)") (class "Default")
      (node (ref "U04B") (pin "4") (pinfunction "NC_4") (pintype "bidirectional"))
    )
    (net (code "117") (name "unconnected-(U04B-NC-Pad8)") (class "Default")
      (node (ref "U04B") (pin "8") (pinfunction "NC_8") (pintype "bidirectional"))
    )
    (net (code "118") (name "unconnected-(U05B-NC-Pad4)") (class "Default")
      (node (ref "U05B") (pin "4") (pinfunction "NC_4") (pintype "bidirectional"))
    )
    (net (code "119") (name "unconnected-(U05B-NC-Pad5)") (class "Default")
      (node (ref "U05B") (pin "5") (pinfunction "NC_5") (pintype "bidirectional"))
    )
    (net (code "120") (name "unconnected-(U06B-+IN1-Pad3)") (class "Default")
      (node (ref "U06B") (pin "3") (pinfunction "+IN1_3") (pintype "input"))
    )
    (net (code "121") (name "unconnected-(U06B--IN1-Pad2)") (class "Default")
      (node (ref "U06B") (pin "2") (pinfunction "-IN1_2") (pintype "input"))
    )
    (net (code "122") (name "unconnected-(U06B-OUT1-Pad1)") (class "Default")
      (node (ref "U06B") (pin "1") (pinfunction "OUT1_1") (pintype "output"))
    )
  )
)
